# sensorboard_22sch.net
KiCad netlist of a schematic drawn in EAGLE
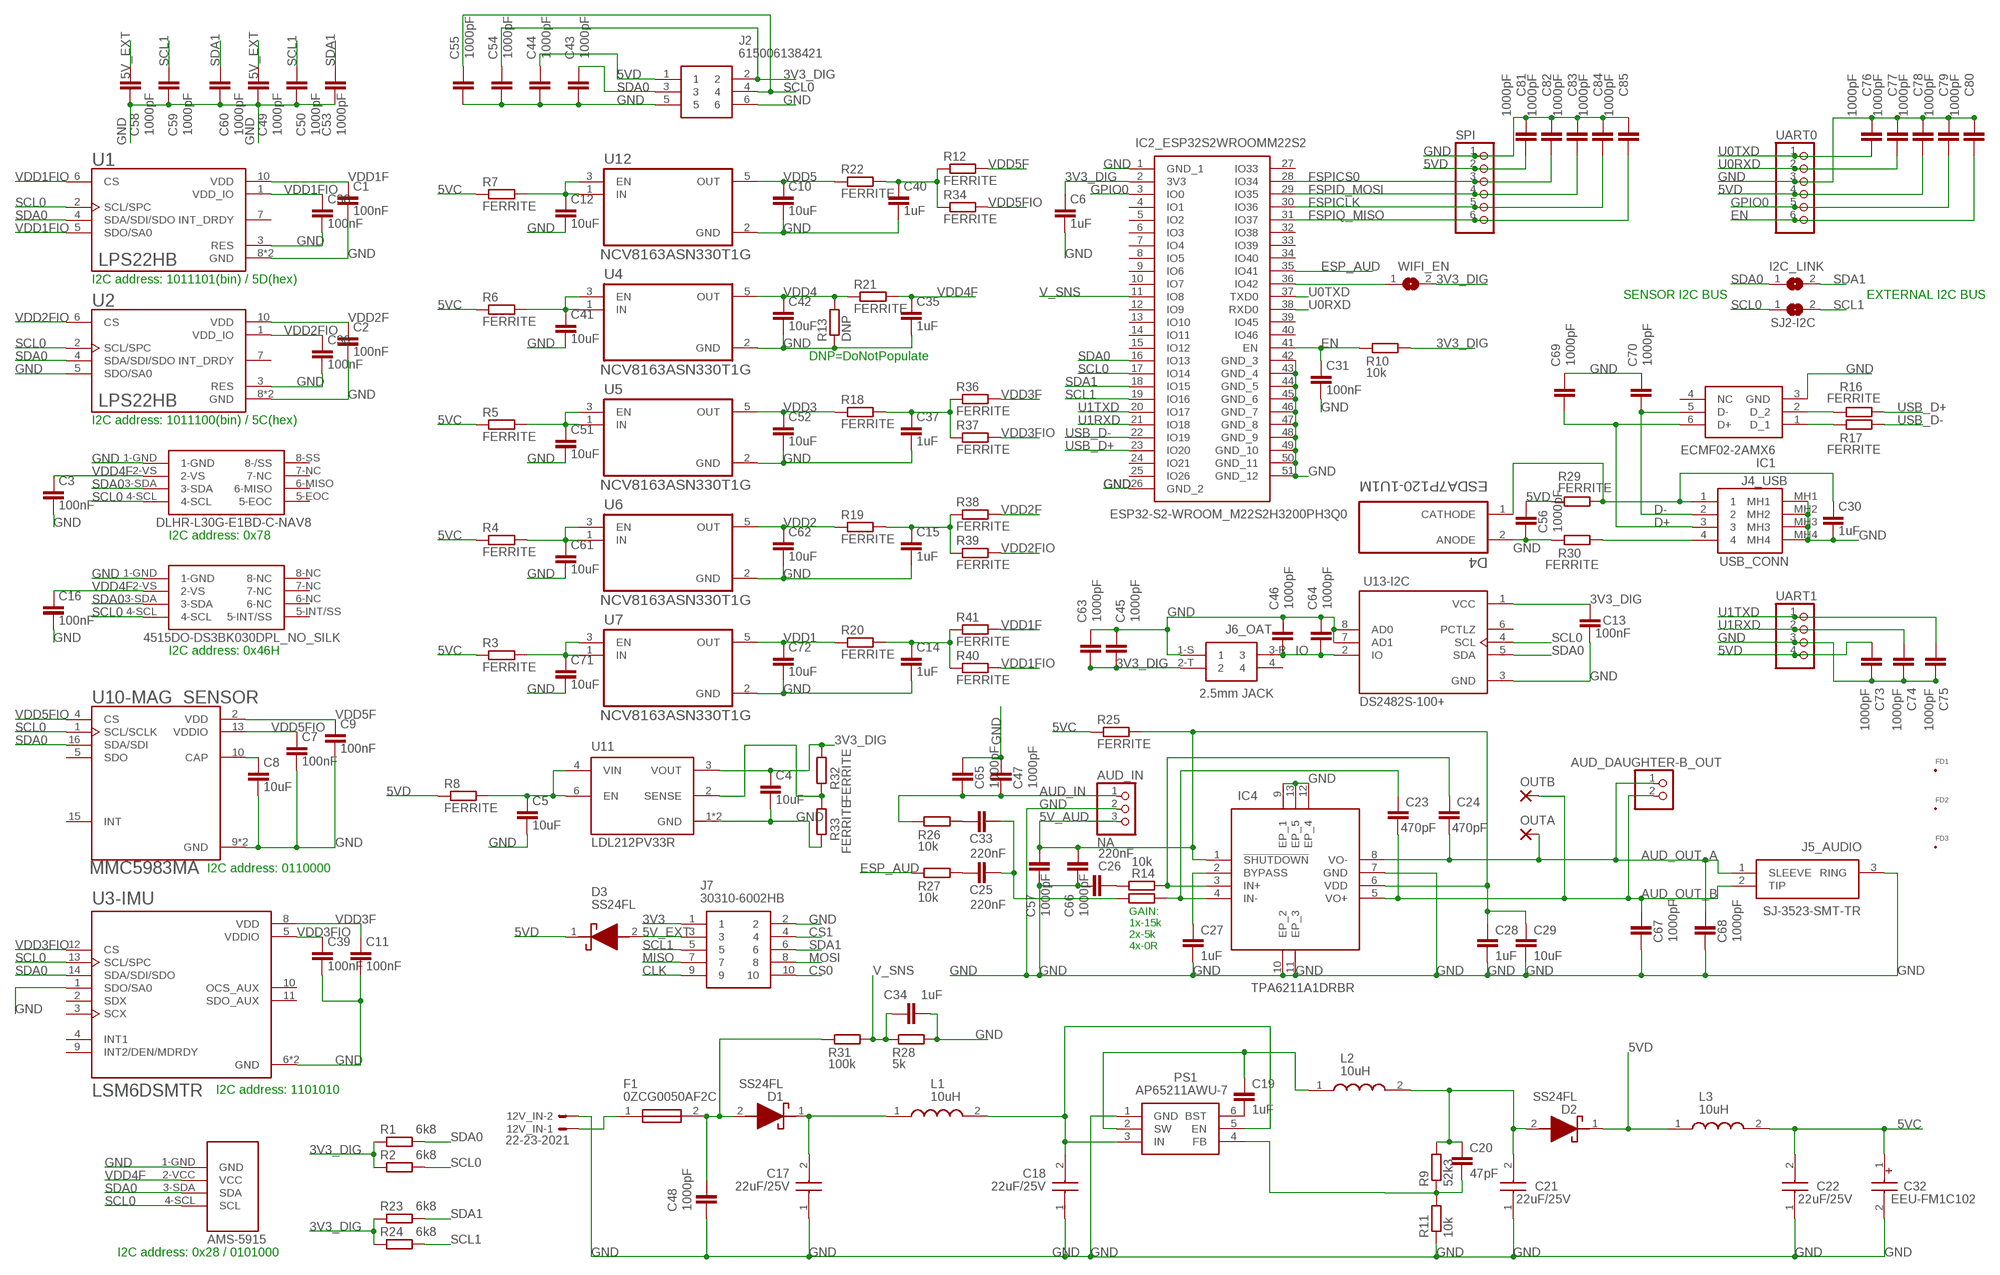
[diagram p0: schematic, sheet 1]

(export (version "E")
  (design (tool "Eeschema 10.0.6"))
  (components
    (comp (ref "12V_IN")
      (value "22-23-2021")
      (footprint "eagle-import:22-23-2021")
      (fields (field (name "MF") "MOLEX"))
      (libsource (lib "eagle-import") (part "22-23-2021"))
    )
    (comp (ref "AUD_DAUGHTER-B_OUT")
      (value "PINHD-1X2")
      (footprint "eagle-import:1X02")
      (libsource (lib "eagle-import") (part "PINHD-1X2"))
    )
    (comp (ref "AUD_IN")
      (value "NA")
      (footprint "eagle-import:1X03")
      (libsource (lib "eagle-import") (part "PINHD-1X3"))
    )
    (comp (ref "C1")
      (value "100nF")
      (footprint "eagle-import:C0402")
      (libsource (lib "eagle-import") (part "C-EUC0402"))
    )
    (comp (ref "C2")
      (value "100nF")
      (footprint "eagle-import:C0402")
      (libsource (lib "eagle-import") (part "C-EUC0402"))
    )
    (comp (ref "C3")
      (value "100nF")
      (footprint "eagle-import:C0402")
      (libsource (lib "eagle-import") (part "C-EUC0402"))
    )
    (comp (ref "C4")
      (value "10uF")
      (footprint "eagle-import:C0805")
      (libsource (lib "eagle-import") (part "C-EUC0805"))
    )
    (comp (ref "C5")
      (value "10uF")
      (footprint "eagle-import:C0805")
      (libsource (lib "eagle-import") (part "C-EUC0805"))
    )
    (comp (ref "C6")
      (value "1uF")
      (footprint "eagle-import:C0603")
      (libsource (lib "eagle-import") (part "C-EUC0603"))
    )
    (comp (ref "C7")
      (value "100nF")
      (footprint "eagle-import:C0402")
      (libsource (lib "eagle-import") (part "C-EUC0402"))
    )
    (comp (ref "C8")
      (value "10uF")
      (footprint "eagle-import:C0805")
      (libsource (lib "eagle-import") (part "C-EUC0805"))
    )
    (comp (ref "C9")
      (value "100nF")
      (footprint "eagle-import:C0402")
      (libsource (lib "eagle-import") (part "C-EUC0402"))
    )
    (comp (ref "C10")
      (value "10uF")
      (footprint "eagle-import:C0805")
      (libsource (lib "eagle-import") (part "C-EUC0805"))
    )
    (comp (ref "C11")
      (value "100nF")
      (footprint "eagle-import:C0402")
      (libsource (lib "eagle-import") (part "C-EUC0402"))
    )
    (comp (ref "C12")
      (value "10uF")
      (footprint "eagle-import:C0805")
      (libsource (lib "eagle-import") (part "C-EUC0805"))
    )
    (comp (ref "C13")
      (value "100nF")
      (footprint "eagle-import:C0402")
      (libsource (lib "eagle-import") (part "C-EUC0402"))
    )
    (comp (ref "C14")
      (value "1uF")
      (footprint "eagle-import:C0603")
      (libsource (lib "eagle-import") (part "C-EUC0603"))
    )
    (comp (ref "C15")
      (value "1uF")
      (footprint "eagle-import:C0603")
      (libsource (lib "eagle-import") (part "C-EUC0603"))
    )
    (comp (ref "C16")
      (value "100nF")
      (footprint "eagle-import:C0402")
      (libsource (lib "eagle-import") (part "C-EUC0402"))
    )
    (comp (ref "C17")
      (value "22uF/25V")
      (footprint "eagle-import:CAPC3216X180N")
      (fields (field (name "MANUFACTURER_PART_NUMBER") "CL31A226KAHNNNE"))
      (libsource (lib "eagle-import") (part "CL31A226KAHNNNE"))
    )
    (comp (ref "C18")
      (value "22uF/25V")
      (footprint "eagle-import:CAPC3216X180N")
      (fields (field (name "MANUFACTURER_PART_NUMBER") "CL31A226KAHNNNE"))
      (libsource (lib "eagle-import") (part "CL31A226KAHNNNE"))
    )
    (comp (ref "C19")
      (value "1uF")
      (footprint "eagle-import:C0603")
      (libsource (lib "eagle-import") (part "C-EUC0603"))
    )
    (comp (ref "C20")
      (value "47pF")
      (footprint "eagle-import:C0402")
      (libsource (lib "eagle-import") (part "C-EUC0402"))
    )
    (comp (ref "C21")
      (value "22uF/25V")
      (footprint "eagle-import:CAPC3216X180N")
      (fields (field (name "MANUFACTURER_PART_NUMBER") "CL31A226KAHNNNE"))
      (libsource (lib "eagle-import") (part "CL31A226KAHNNNE"))
    )
    (comp (ref "C22")
      (value "22uF/25V")
      (footprint "eagle-import:CAPC3216X180N")
      (fields (field (name "MANUFACTURER_PART_NUMBER") "CL31A226KAHNNNE"))
      (libsource (lib "eagle-import") (part "CL31A226KAHNNNE"))
    )
    (comp (ref "C23")
      (value "470pF")
      (footprint "eagle-import:C0805")
      (libsource (lib "eagle-import") (part "C-EUC0805"))
    )
    (comp (ref "C24")
      (value "470pF")
      (footprint "eagle-import:C0805")
      (libsource (lib "eagle-import") (part "C-EUC0805"))
    )
    (comp (ref "C25")
      (value "220nF")
      (footprint "eagle-import:C1206")
      (libsource (lib "eagle-import") (part "C-EUC1206"))
    )
    (comp (ref "C26")
      (value "220nF")
      (footprint "eagle-import:C1206")
      (libsource (lib "eagle-import") (part "C-EUC1206"))
    )
    (comp (ref "C27")
      (value "1uF")
      (footprint "eagle-import:C0603")
      (libsource (lib "eagle-import") (part "C-EUC0603"))
    )
    (comp (ref "C28")
      (value "1uF")
      (footprint "eagle-import:C0603")
      (libsource (lib "eagle-import") (part "C-EUC0603"))
    )
    (comp (ref "C29")
      (value "10uF")
      (footprint "eagle-import:C0805")
      (libsource (lib "eagle-import") (part "C-EUC0805"))
    )
    (comp (ref "C30")
      (value "1uF")
      (footprint "eagle-import:C0603")
      (libsource (lib "eagle-import") (part "C-EUC0603"))
    )
    (comp (ref "C31")
      (value "100nF")
      (footprint "eagle-import:C0402")
      (libsource (lib "eagle-import") (part "C-EUC0402"))
    )
    (comp (ref "C32")
      (value "EEU-FM1C102")
      (footprint "eagle-import:CAPPRD500W65D1000H2200")
      (fields (field (name "MOUSER_PART_NUMBER") "667-EEU-FM1C102"))
      (libsource (lib "eagle-import") (part "EEU-FM1C102"))
    )
    (comp (ref "C33")
      (value "220nF")
      (footprint "eagle-import:C1206")
      (libsource (lib "eagle-import") (part "C-EUC1206"))
    )
    (comp (ref "C34")
      (value "1uF")
      (footprint "eagle-import:C0603")
      (libsource (lib "eagle-import") (part "C-EUC0603"))
    )
    (comp (ref "C35")
      (value "1uF")
      (footprint "eagle-import:C0603")
      (libsource (lib "eagle-import") (part "C-EUC0603"))
    )
    (comp (ref "C36")
      (value "100nF")
      (footprint "eagle-import:C0402")
      (libsource (lib "eagle-import") (part "C-EUC0402"))
    )
    (comp (ref "C37")
      (value "1uF")
      (footprint "eagle-import:C0603")
      (libsource (lib "eagle-import") (part "C-EUC0603"))
    )
    (comp (ref "C38")
      (value "100nF")
      (footprint "eagle-import:C0402")
      (libsource (lib "eagle-import") (part "C-EUC0402"))
    )
    (comp (ref "C39")
      (value "100nF")
      (footprint "eagle-import:C0402")
      (libsource (lib "eagle-import") (part "C-EUC0402"))
    )
    (comp (ref "C40")
      (value "1uF")
      (footprint "eagle-import:C0603")
      (libsource (lib "eagle-import") (part "C-EUC0603"))
    )
    (comp (ref "C41")
      (value "10uF")
      (footprint "eagle-import:C0805")
      (libsource (lib "eagle-import") (part "C-EUC0805"))
    )
    (comp (ref "C42")
      (value "10uF")
      (footprint "eagle-import:C0805")
      (libsource (lib "eagle-import") (part "C-EUC0805"))
    )
    (comp (ref "C43")
      (value "1000pF")
      (footprint "eagle-import:C0402")
      (libsource (lib "eagle-import") (part "C-EUC0402"))
    )
    (comp (ref "C44")
      (value "1000pF")
      (footprint "eagle-import:C0402")
      (libsource (lib "eagle-import") (part "C-EUC0402"))
    )
    (comp (ref "C45")
      (value "1000pF")
      (footprint "eagle-import:C0402")
      (libsource (lib "eagle-import") (part "C-EUC0402"))
    )
    (comp (ref "C46")
      (value "1000pF")
      (footprint "eagle-import:C0402")
      (libsource (lib "eagle-import") (part "C-EUC0402"))
    )
    (comp (ref "C47")
      (value "1000pF")
      (footprint "eagle-import:C0402")
      (libsource (lib "eagle-import") (part "C-EUC0402"))
    )
    (comp (ref "C48")
      (value "1000pF")
      (footprint "eagle-import:C0402")
      (libsource (lib "eagle-import") (part "C-EUC0402"))
    )
    (comp (ref "C49")
      (value "1000pF")
      (footprint "eagle-import:C0402")
      (libsource (lib "eagle-import") (part "C-EUC0402"))
    )
    (comp (ref "C50")
      (value "1000pF")
      (footprint "eagle-import:C0402")
      (libsource (lib "eagle-import") (part "C-EUC0402"))
    )
    (comp (ref "C51")
      (value "10uF")
      (footprint "eagle-import:C0805")
      (libsource (lib "eagle-import") (part "C-EUC0805"))
    )
    (comp (ref "C52")
      (value "10uF")
      (footprint "eagle-import:C0805")
      (libsource (lib "eagle-import") (part "C-EUC0805"))
    )
    (comp (ref "C53")
      (value "1000pF")
      (footprint "eagle-import:C0402")
      (libsource (lib "eagle-import") (part "C-EUC0402"))
    )
    (comp (ref "C54")
      (value "1000pF")
      (footprint "eagle-import:C0402")
      (libsource (lib "eagle-import") (part "C-EUC0402"))
    )
    (comp (ref "C55")
      (value "1000pF")
      (footprint "eagle-import:C0402")
      (libsource (lib "eagle-import") (part "C-EUC0402"))
    )
    (comp (ref "C56")
      (value "1000pF")
      (footprint "eagle-import:C0402")
      (libsource (lib "eagle-import") (part "C-EUC0402"))
    )
    (comp (ref "C57")
      (value "1000pF")
      (footprint "eagle-import:C0402")
      (libsource (lib "eagle-import") (part "C-EUC0402"))
    )
    (comp (ref "C58")
      (value "1000pF")
      (footprint "eagle-import:C0402")
      (libsource (lib "eagle-import") (part "C-EUC0402"))
    )
    (comp (ref "C59")
      (value "1000pF")
      (footprint "eagle-import:C0402")
      (libsource (lib "eagle-import") (part "C-EUC0402"))
    )
    (comp (ref "C60")
      (value "1000pF")
      (footprint "eagle-import:C0402")
      (libsource (lib "eagle-import") (part "C-EUC0402"))
    )
    (comp (ref "C61")
      (value "10uF")
      (footprint "eagle-import:C0805")
      (libsource (lib "eagle-import") (part "C-EUC0805"))
    )
    (comp (ref "C62")
      (value "10uF")
      (footprint "eagle-import:C0805")
      (libsource (lib "eagle-import") (part "C-EUC0805"))
    )
    (comp (ref "C63")
      (value "1000pF")
      (footprint "eagle-import:C0402")
      (libsource (lib "eagle-import") (part "C-EUC0402"))
    )
    (comp (ref "C64")
      (value "1000pF")
      (footprint "eagle-import:C0402")
      (libsource (lib "eagle-import") (part "C-EUC0402"))
    )
    (comp (ref "C65")
      (value "1000pF")
      (footprint "eagle-import:C0402")
      (libsource (lib "eagle-import") (part "C-EUC0402"))
    )
    (comp (ref "C66")
      (value "1000pF")
      (footprint "eagle-import:C0402")
      (libsource (lib "eagle-import") (part "C-EUC0402"))
    )
    (comp (ref "C67")
      (value "1000pF")
      (footprint "eagle-import:C0402")
      (libsource (lib "eagle-import") (part "C-EUC0402"))
    )
    (comp (ref "C68")
      (value "1000pF")
      (footprint "eagle-import:C0402")
      (libsource (lib "eagle-import") (part "C-EUC0402"))
    )
    (comp (ref "C69")
      (value "1000pF")
      (footprint "eagle-import:C0402")
      (libsource (lib "eagle-import") (part "C-EUC0402"))
    )
    (comp (ref "C70")
      (value "1000pF")
      (footprint "eagle-import:C0402")
      (libsource (lib "eagle-import") (part "C-EUC0402"))
    )
    (comp (ref "C71")
      (value "10uF")
      (footprint "eagle-import:C0805")
      (libsource (lib "eagle-import") (part "C-EUC0805"))
    )
    (comp (ref "C72")
      (value "10uF")
      (footprint "eagle-import:C0805")
      (libsource (lib "eagle-import") (part "C-EUC0805"))
    )
    (comp (ref "C73")
      (value "1000pF")
      (footprint "eagle-import:C0402")
      (libsource (lib "eagle-import") (part "C-EUC0402"))
    )
    (comp (ref "C74")
      (value "1000pF")
      (footprint "eagle-import:C0402")
      (libsource (lib "eagle-import") (part "C-EUC0402"))
    )
    (comp (ref "C75")
      (value "1000pF")
      (footprint "eagle-import:C0402")
      (libsource (lib "eagle-import") (part "C-EUC0402"))
    )
    (comp (ref "C76")
      (value "1000pF")
      (footprint "eagle-import:C0402")
      (libsource (lib "eagle-import") (part "C-EUC0402"))
    )
    (comp (ref "C77")
      (value "1000pF")
      (footprint "eagle-import:C0402")
      (libsource (lib "eagle-import") (part "C-EUC0402"))
    )
    (comp (ref "C78")
      (value "1000pF")
      (footprint "eagle-import:C0402")
      (libsource (lib "eagle-import") (part "C-EUC0402"))
    )
    (comp (ref "C79")
      (value "1000pF")
      (footprint "eagle-import:C0402")
      (libsource (lib "eagle-import") (part "C-EUC0402"))
    )
    (comp (ref "C80")
      (value "1000pF")
      (footprint "eagle-import:C0402")
      (libsource (lib "eagle-import") (part "C-EUC0402"))
    )
    (comp (ref "C81")
      (value "1000pF")
      (footprint "eagle-import:C0402")
      (libsource (lib "eagle-import") (part "C-EUC0402"))
    )
    (comp (ref "C82")
      (value "1000pF")
      (footprint "eagle-import:C0402")
      (libsource (lib "eagle-import") (part "C-EUC0402"))
    )
    (comp (ref "C83")
      (value "1000pF")
      (footprint "eagle-import:C0402")
      (libsource (lib "eagle-import") (part "C-EUC0402"))
    )
    (comp (ref "C84")
      (value "1000pF")
      (footprint "eagle-import:C0402")
      (libsource (lib "eagle-import") (part "C-EUC0402"))
    )
    (comp (ref "C85")
      (value "1000pF")
      (footprint "eagle-import:C0402")
      (libsource (lib "eagle-import") (part "C-EUC0402"))
    )
    (comp (ref "D1")
      (value "SS24FL")
      (footprint "eagle-import:SODFL3617X108N")
      (fields (field (name "MOUSER_PART_NUMBER") "512-SS24FL"))
      (libsource (lib "eagle-import") (part "SS24FL"))
    )
    (comp (ref "D2")
      (value "SS24FL")
      (footprint "eagle-import:SODFL3617X108N")
      (fields (field (name "MOUSER_PART_NUMBER") "512-SS24FL"))
      (libsource (lib "eagle-import") (part "SS24FL"))
    )
    (comp (ref "D3")
      (value "SS24FL")
      (footprint "eagle-import:SODFL3617X108N")
      (fields (field (name "MOUSER_PART_NUMBER") "512-SS24FL"))
      (libsource (lib "eagle-import") (part "SS24FL"))
    )
    (comp (ref "D4")
      (value "ESDA7P120-1U1M")
      (footprint "eagle-import:DIO_ESDA13P70-1U1M")
      (fields (field (name "MF") "STMicroelectronics"))
      (libsource (lib "eagle-import") (part "ESDA7P120-1U1M"))
    )
    (comp (ref "DLHR-L30G-E1BD-C-NAV8")
      (value "DLHR-L30G-E1BD-C-NAV8")
      (footprint "eagle-import:DLHR-L30G-E1BD-C-NAV8")
      (libsource (lib "eagle-import") (part "DLHR-L30G-E1BD-C-NAV8"))
    )
    (comp (ref "F1")
      (value "0ZCG0050AF2C")
      (footprint "eagle-import:FUSC4632X75N")
      (fields (field (name "MOUSER_PART_NUMBER") "530-0ZCG0050AF2C"))
      (libsource (lib "eagle-import") (part "0ZCG0050AF2C"))
    )
    (comp (ref "FD1")
      (value "FID_20MIL_P")
      (footprint "eagle-import:FID_020_P")
      (libsource (lib "eagle-import") (part "FID_20MIL_P"))
    )
    (comp (ref "FD2")
      (value "FID_20MIL_P")
      (footprint "eagle-import:FID_020_P")
      (libsource (lib "eagle-import") (part "FID_20MIL_P"))
    )
    (comp (ref "FD3")
      (value "FID_20MIL_P")
      (footprint "eagle-import:FID_020_P")
      (libsource (lib "eagle-import") (part "FID_20MIL_P"))
    )
    (comp (ref "I2C_LINK")
      (value "SJ")
      (footprint "eagle-import:SJ")
      (libsource (lib "eagle-import") (part "SJ"))
    )
    (comp (ref "IC1")
      (value "ECMF02-2AMX6")
      (footprint "eagle-import:SON50P150X170X55-6N")
      (fields (field (name "MF") "STMicroelectronics"))
      (libsource (lib "eagle-import") (part "ECMF02-2AMX6"))
    )
    (comp (ref "IC2_ESP32S2WROOMM22S2")
      (value "ESP32-S2-WROOM_M22S2H3200PH3Q0")
      (footprint "eagle-import:ESP32S2WROOMM22S2H3200PH3Q0")
      (fields
        (field (name "MANUFACTURER_PART_NUMBER") "ESP32-S2-WROOM(M22S2H3200PH3Q0)")
        (field (name "MOUSER_PART_NUMBER") "356-ESP32S2WRM3200PH")
      )
      (libsource (lib "eagle-import") (part "ESP32-S2-WROOM_M22S2H3200PH3Q0"))
    )
    (comp (ref "IC4")
      (value "TPA6211A1DRBR")
      (footprint "eagle-import:TPS7A8033DRBT")
      (fields (field (name "MOUSER_PART_NUMBER") "595-TPA6211A1DRBR"))
      (libsource (lib "eagle-import") (part "TPA6211A1DRBR"))
    )
    (comp (ref "J2")
      (value "615006138421")
      (footprint "eagle-import:615006138421")
      (fields (field (name "MOUSER_PART_NUMBER") "710-615006138421"))
      (libsource (lib "eagle-import") (part "615006138421"))
    )
    (comp (ref "J4_USB")
      (value "USB_CONN")
      (footprint "eagle-import:737250110BLF")
      (fields
        (field (name "MANUFACTURER_PART_NUMBER") "73725-0110BLF")
        (field (name "MOUSER_PART_NUMBER") "649-73725-0110BLF")
      )
      (libsource (lib "eagle-import") (part "73725-0110BLF"))
    )
    (comp (ref "J5_AUDIO")
      (value "SJ-3523-SMT-TR")
      (footprint "eagle-import:SJ3523SMTTR")
      (fields (field (name "MOUSER_PART_NUMBER") "490-SJ-3523-SMT-TR"))
      (libsource (lib "eagle-import") (part "SJ-3523-SMT-TR"))
    )
    (comp (ref "J6_OAT")
      (value "2.5mm JACK")
      (footprint "eagle-import:SJ-2523-SMT-TR")
      (fields
        (field (name "MANUFACTURER_PART_NUMBER") "SJ-2523-SMT-TR")
        (field (name "MOUSER_PART_NUMBER") "490-SJ-2523-SMT-TR")
      )
      (libsource (lib "eagle-import") (part "SJ-2523-SMT-TR"))
    )
    (comp (ref "J7")
      (value "30310-6002HB")
      (footprint "eagle-import:SHDR10W64P254_2X5_2030X878X930")
      (fields (field (name "MOUSER_PART_NUMBER") "517-30310-6002"))
      (libsource (lib "eagle-import") (part "30310-6002HB"))
    )
    (comp (ref "L1")
      (value "10uH")
      (footprint "eagle-import:FDSD0420WH150MP3")
      (fields
        (field (name "MANUFACTURER_PART_NUMBER") "FDSD0420-H-100M=P3")
        (field (name "MOUSER_PART_NUMBER") "81-FDSD0420-H-100MP3")
      )
      (libsource (lib "eagle-import") (part "FDSD0420-H-100M=P3"))
    )
    (comp (ref "L2")
      (value "10uH")
      (footprint "eagle-import:FDSD0420WH150MP3")
      (fields
        (field (name "MANUFACTURER_PART_NUMBER") "FDSD0420-H-100M=P3")
        (field (name "MOUSER_PART_NUMBER") "81-FDSD0420-H-100MP3")
      )
      (libsource (lib "eagle-import") (part "FDSD0420-H-100M=P3"))
    )
    (comp (ref "L3")
      (value "10uH")
      (footprint "eagle-import:FDSD0420WH150MP3")
      (fields
        (field (name "MANUFACTURER_PART_NUMBER") "FDSD0420-H-100M=P3")
        (field (name "MOUSER_PART_NUMBER") "81-FDSD0420-H-100MP3")
      )
      (libsource (lib "eagle-import") (part "FDSD0420-H-100M=P3"))
    )
    (comp (ref "OUTA")
      (value "SMD2_SMALLSMALL")
      (footprint "eagle-import:SMD2_SMALL")
      (libsource (lib "eagle-import") (part "SMD2_SMALLSMALL"))
    )
    (comp (ref "OUTB")
      (value "SMD2_SMALLSMALL")
      (footprint "eagle-import:SMD2_SMALL")
      (libsource (lib "eagle-import") (part "SMD2_SMALLSMALL"))
    )
    (comp (ref "PS1")
      (value "AP65211AWU-7")
      (footprint "eagle-import:SOT95P280X90-6N")
      (fields (field (name "MOUSER_PART_NUMBER") "621-AP65211AWU-7"))
      (libsource (lib "eagle-import") (part "AP65211AWU-7"))
    )
    (comp (ref "R1")
      (value "6k8")
      (footprint "eagle-import:R0402")
      (libsource (lib "eagle-import") (part "R-EU_R0402"))
    )
    (comp (ref "R2")
      (value "6k8")
      (footprint "eagle-import:R0402")
      (libsource (lib "eagle-import") (part "R-EU_R0402"))
    )
    (comp (ref "R3")
      (value "FERRITE")
      (footprint "eagle-import:R0805")
      (libsource (lib "eagle-import") (part "R-EU_R0805"))
    )
    (comp (ref "R4")
      (value "FERRITE")
      (footprint "eagle-import:R0805")
      (libsource (lib "eagle-import") (part "R-EU_R0805"))
    )
    (comp (ref "R5")
      (value "FERRITE")
      (footprint "eagle-import:R0805")
      (libsource (lib "eagle-import") (part "R-EU_R0805"))
    )
    (comp (ref "R6")
      (value "FERRITE")
      (footprint "eagle-import:R0805")
      (libsource (lib "eagle-import") (part "R-EU_R0805"))
    )
    (comp (ref "R7")
      (value "FERRITE")
      (footprint "eagle-import:R0805")
      (libsource (lib "eagle-import") (part "R-EU_R0805"))
    )
    (comp (ref "R8")
      (value "FERRITE")
      (footprint "eagle-import:R0805")
      (libsource (lib "eagle-import") (part "R-EU_R0805"))
    )
    (comp (ref "R9")
      (value "52k3")
      (footprint "eagle-import:R0402")
      (libsource (lib "eagle-import") (part "R-EU_R0402"))
    )
    (comp (ref "R10")
      (value "10k")
      (footprint "eagle-import:R0402")
      (libsource (lib "eagle-import") (part "R-EU_R0402"))
    )
    (comp (ref "R11")
      (value "10k")
      (footprint "eagle-import:R0402")
      (libsource (lib "eagle-import") (part "R-EU_R0402"))
    )
    (comp (ref "R12")
      (value "FERRITE")
      (footprint "eagle-import:R0805")
      (libsource (lib "eagle-import") (part "R-EU_R0805"))
    )
    (comp (ref "R13")
      (value "DNP")
      (footprint "eagle-import:R0805")
      (libsource (lib "eagle-import") (part "R-EU_R0805"))
    )
    (comp (ref "R14")
      (value "10k")
      (footprint "eagle-import:R0402")
      (libsource (lib "eagle-import") (part "R-EU_R0402"))
    )
    (comp (ref "R15")
      (value "R-EU_R0402")
      (footprint "eagle-import:R0402")
      (libsource (lib "eagle-import") (part "R-EU_R0402"))
    )
    (comp (ref "R16")
      (value "FERRITE")
      (footprint "eagle-import:R0805")
      (libsource (lib "eagle-import") (part "R-EU_R0805"))
    )
    (comp (ref "R17")
      (value "FERRITE")
      (footprint "eagle-import:R0805")
      (libsource (lib "eagle-import") (part "R-EU_R0805"))
    )
    (comp (ref "R18")
      (value "FERRITE")
      (footprint "eagle-import:R0805")
      (libsource (lib "eagle-import") (part "R-EU_R0805"))
    )
    (comp (ref "R19")
      (value "FERRITE")
      (footprint "eagle-import:R0805")
      (libsource (lib "eagle-import") (part "R-EU_R0805"))
    )
    (comp (ref "R20")
      (value "FERRITE")
      (footprint "eagle-import:R0805")
      (libsource (lib "eagle-import") (part "R-EU_R0805"))
    )
    (comp (ref "R21")
      (value "FERRITE")
      (footprint "eagle-import:R0805")
      (libsource (lib "eagle-import") (part "R-EU_R0805"))
    )
    (comp (ref "R22")
      (value "FERRITE")
      (footprint "eagle-import:R0805")
      (libsource (lib "eagle-import") (part "R-EU_R0805"))
    )
    (comp (ref "R23")
      (value "6k8")
      (footprint "eagle-import:R0402")
      (libsource (lib "eagle-import") (part "R-EU_R0402"))
    )
    (comp (ref "R24")
      (value "6k8")
      (footprint "eagle-import:R0402")
      (libsource (lib "eagle-import") (part "R-EU_R0402"))
    )
    (comp (ref "R25")
      (value "FERRITE")
      (footprint "eagle-import:R0805")
      (libsource (lib "eagle-import") (part "R-EU_R0805"))
    )
    (comp (ref "R26")
      (value "10k")
      (footprint "eagle-import:R0402")
      (libsource (lib "eagle-import") (part "R-EU_R0402"))
    )
    (comp (ref "R27")
      (value "10k")
      (footprint "eagle-import:R0402")
      (libsource (lib "eagle-import") (part "R-EU_R0402"))
    )
    (comp (ref "R28")
      (value "5k")
      (footprint "eagle-import:R0402")
      (libsource (lib "eagle-import") (part "R-EU_R0402"))
    )
    (comp (ref "R29")
      (value "FERRITE")
      (footprint "eagle-import:R0805")
      (libsource (lib "eagle-import") (part "R-EU_R0805"))
    )
    (comp (ref "R30")
      (value "FERRITE")
      (footprint "eagle-import:R0805")
      (libsource (lib "eagle-import") (part "R-EU_R0805"))
    )
    (comp (ref "R31")
      (value "100k")
      (footprint "eagle-import:R0402")
      (libsource (lib "eagle-import") (part "R-EU_R0402"))
    )
    (comp (ref "R32")
      (value "FERRITE")
      (footprint "eagle-import:R0402")
      (libsource (lib "eagle-import") (part "R-EU_R0402"))
    )
    (comp (ref "R33")
      (value "FERRITE")
      (footprint "eagle-import:R0402")
      (libsource (lib "eagle-import") (part "R-EU_R0402"))
    )
    (comp (ref "R34")
      (value "FERRITE")
      (footprint "eagle-import:R0805")
      (libsource (lib "eagle-import") (part "R-EU_R0805"))
    )
    (comp (ref "R36")
      (value "FERRITE")
      (footprint "eagle-import:R0805")
      (libsource (lib "eagle-import") (part "R-EU_R0805"))
    )
    (comp (ref "R37")
      (value "FERRITE")
      (footprint "eagle-import:R0805")
      (libsource (lib "eagle-import") (part "R-EU_R0805"))
    )
    (comp (ref "R38")
      (value "FERRITE")
      (footprint "eagle-import:R0805")
      (libsource (lib "eagle-import") (part "R-EU_R0805"))
    )
    (comp (ref "R39")
      (value "FERRITE")
      (footprint "eagle-import:R0805")
      (libsource (lib "eagle-import") (part "R-EU_R0805"))
    )
    (comp (ref "R40")
      (value "FERRITE")
      (footprint "eagle-import:R0805")
      (libsource (lib "eagle-import") (part "R-EU_R0805"))
    )
    (comp (ref "R41")
      (value "FERRITE")
      (footprint "eagle-import:R0805")
      (libsource (lib "eagle-import") (part "R-EU_R0805"))
    )
    (comp (ref "SJ2-I2C")
      (value "SJ")
      (footprint "eagle-import:SJ")
      (libsource (lib "eagle-import") (part "SJ"))
    )
    (comp (ref "SPI")
      (value "PINHD-1X6")
      (footprint "eagle-import:1X06")
      (libsource (lib "eagle-import") (part "PINHD-1X6"))
    )
    (comp (ref "U$1")
      (value "AMS-5915")
      (footprint "eagle-import:AMS-5915")
      (libsource (lib "eagle-import") (part "AMS-5915"))
    )
    (comp (ref "U$4")
      (value "4515DO-DS3BK030DPL_NO_SILKNO_SILK")
      (footprint "eagle-import:4515DO-DS3BK030DPL_NO_SILK")
      (libsource (lib "eagle-import") (part "4515DO-DS3BK030DPL_NO_SILKNO_SILK"))
    )
    (comp (ref "U1")
      (value "LPS22HB")
      (footprint "eagle-import:LGA10R50P2X3_200X200X80")
      (fields (field (name "MF") "STMicroelectronics"))
      (libsource (lib "eagle-import") (part "LPS22HB"))
    )
    (comp (ref "U2")
      (value "LPS22HB")
      (footprint "eagle-import:LGA10R50P2X3_200X200X80")
      (fields (field (name "MF") "STMicroelectronics"))
      (libsource (lib "eagle-import") (part "LPS22HB"))
    )
    (comp (ref "U3-IMU")
      (value "LSM6DSMTR")
      (footprint "eagle-import:PQFN50P300X250X86-14N")
      (fields (field (name "MF") "STMicroelectronics"))
      (libsource (lib "eagle-import") (part "LSM6DSMTR"))
    )
    (comp (ref "U4")
      (value "NCV8163ASN330T1G")
      (footprint "eagle-import:SOP95P275X110-5N")
      (fields (field (name "MF") "ON Semiconductor"))
      (libsource (lib "eagle-import") (part "NCV8163ASN330T1G"))
    )
    (comp (ref "U5")
      (value "NCV8163ASN330T1G")
      (footprint "eagle-import:SOP95P275X110-5N")
      (fields (field (name "MF") "ON Semiconductor"))
      (libsource (lib "eagle-import") (part "NCV8163ASN330T1G"))
    )
    (comp (ref "U6")
      (value "NCV8163ASN330T1G")
      (footprint "eagle-import:SOP95P275X110-5N")
      (fields (field (name "MF") "ON Semiconductor"))
      (libsource (lib "eagle-import") (part "NCV8163ASN330T1G"))
    )
    (comp (ref "U7")
      (value "NCV8163ASN330T1G")
      (footprint "eagle-import:SOP95P275X110-5N")
      (fields (field (name "MF") "ON Semiconductor"))
      (libsource (lib "eagle-import") (part "NCV8163ASN330T1G"))
    )
    (comp (ref "U10-MAG_SENSOR")
      (value "MMC5983MA")
      (footprint "eagle-import:LGA16R50P4X4_330X330X100")
      (fields (field (name "MF") "ON Semiconductor") (field (name "MP") "FIS1100"))
      (libsource (lib "eagle-import") (part "MMC5983MA"))
    )
    (comp (ref "U11")
      (value "LDL212PV33R")
      (footprint "eagle-import:SON50P200X200X80-7N")
      (fields (field (name "MF") "STMicroelectronics"))
      (libsource (lib "eagle-import") (part "LDL212PV33R"))
    )
    (comp (ref "U12")
      (value "NCV8163ASN330T1G")
      (footprint "eagle-import:SOP95P275X110-5N")
      (fields (field (name "MF") "ON Semiconductor"))
      (libsource (lib "eagle-import") (part "NCV8163ASN330T1G"))
    )
    (comp (ref "U13-I2C")
      (value "DS2482S-100+")
      (footprint "eagle-import:SOIC127P600X175-8N")
      (fields (field (name "MF") "Maxim Integrated"))
      (libsource (lib "eagle-import") (part "DS2482S-100+"))
    )
    (comp (ref "UART0")
      (value "PINHD-1X6")
      (footprint "eagle-import:1X06")
      (libsource (lib "eagle-import") (part "PINHD-1X6"))
    )
    (comp (ref "UART1")
      (value "PINHD-1X4")
      (footprint "eagle-import:1X04")
      (libsource (lib "eagle-import") (part "PINHD-1X4"))
    )
    (comp (ref "WIFI_EN")
      (value "SJ")
      (footprint "eagle-import:SJ")
      (libsource (lib "eagle-import") (part "SJ"))
    )
  )
  (nets
    (net (code "1") (name "/3V3") (class "Default")
      (node (ref "J7") (pin "1") (pinfunction "1_1") (pintype "bidirectional"))
    )
    (net (code "2") (name "/3V3_DIG") (class "Default")
      (node (ref "C13") (pin "1") (pinfunction "1_1") (pintype "passive"))
      (node (ref "C4") (pin "1") (pinfunction "1_1") (pintype "passive"))
      (node (ref "C45") (pin "1") (pinfunction "1_1") (pintype "passive"))
      (node (ref "C54") (pin "2") (pinfunction "2_2") (pintype "passive"))
      (node (ref "C6") (pin "1") (pinfunction "1_1") (pintype "passive"))
      (node (ref "C63") (pin "1") (pinfunction "1_1") (pintype "passive"))
      (node (ref "IC2_ESP32S2WROOMM22S2") (pin "2") (pinfunction "3V3_2") (pintype "bidirectional"))
      (node (ref "J2") (pin "2") (pinfunction "2_2") (pintype "bidirectional"))
      (node (ref "J6_OAT") (pin "2-T") (pinfunction "2_2-T") (pintype "bidirectional"))
      (node (ref "R1") (pin "1") (pinfunction "1_1") (pintype "passive"))
      (node (ref "R10") (pin "2") (pinfunction "2_2") (pintype "passive"))
      (node (ref "R2") (pin "1") (pinfunction "1_1") (pintype "passive"))
      (node (ref "R23") (pin "1") (pinfunction "1_1") (pintype "passive"))
      (node (ref "R24") (pin "1") (pinfunction "1_1") (pintype "passive"))
      (node (ref "R32") (pin "2") (pinfunction "2_2") (pintype "passive"))
      (node (ref "U11") (pin "3") (pinfunction "VOUT_3") (pintype "output"))
      (node (ref "U13-I2C") (pin "1") (pinfunction "VCC_1") (pintype "power_in"))
      (node (ref "WIFI_EN") (pin "2") (pinfunction "2_2") (pintype "passive"))
    )
    (net (code "3") (name "/5VC") (class "Default")
      (node (ref "C22") (pin "2") (pinfunction "2_2") (pintype "bidirectional"))
      (node (ref "C32") (pin "1") (pinfunction "+_1") (pintype "bidirectional"))
      (node (ref "L3") (pin "2") (pinfunction "2_2") (pintype "bidirectional"))
      (node (ref "R25") (pin "1") (pinfunction "1_1") (pintype "passive"))
      (node (ref "R3") (pin "1") (pinfunction "1_1") (pintype "passive"))
      (node (ref "R4") (pin "1") (pinfunction "1_1") (pintype "passive"))
      (node (ref "R5") (pin "1") (pinfunction "1_1") (pintype "passive"))
      (node (ref "R6") (pin "1") (pinfunction "1_1") (pintype "passive"))
      (node (ref "R7") (pin "1") (pinfunction "1_1") (pintype "passive"))
    )
    (net (code "4") (name "/5VD") (class "Default")
      (node (ref "C44") (pin "2") (pinfunction "2_2") (pintype "passive"))
      (node (ref "C56") (pin "2") (pinfunction "2_2") (pintype "passive"))
      (node (ref "C73") (pin "1") (pinfunction "1_1") (pintype "passive"))
      (node (ref "C78") (pin "2") (pinfunction "2_2") (pintype "passive"))
      (node (ref "C81") (pin "2") (pinfunction "2_2") (pintype "passive"))
      (node (ref "D2") (pin "1") (pinfunction "K_1") (pintype "bidirectional"))
      (node (ref "D3") (pin "1") (pinfunction "K_1") (pintype "bidirectional"))
      (node (ref "J2") (pin "1") (pinfunction "1_1") (pintype "bidirectional"))
      (node (ref "L3") (pin "1") (pinfunction "1_1") (pintype "bidirectional"))
      (node (ref "R29") (pin "1") (pinfunction "1_1") (pintype "passive"))
      (node (ref "R8") (pin "1") (pinfunction "1_1") (pintype "passive"))
      (node (ref "SPI") (pin "2") (pinfunction "2_2") (pintype "passive"))
      (node (ref "UART0") (pin "4") (pinfunction "4_4") (pintype "passive"))
      (node (ref "UART1") (pin "4") (pinfunction "4_4") (pintype "passive"))
    )
    (net (code "5") (name "/5V_AUD") (class "Default")
      (node (ref "AUD_IN") (pin "3") (pinfunction "3_3") (pintype "passive"))
      (node (ref "C28") (pin "1") (pinfunction "1_1") (pintype "passive"))
      (node (ref "C29") (pin "1") (pinfunction "1_1") (pintype "passive"))
      (node (ref "C57") (pin "2") (pinfunction "2_2") (pintype "passive"))
      (node (ref "C66") (pin "2") (pinfunction "2_2") (pintype "passive"))
      (node (ref "IC4") (pin "1") (pinfunction "~{SHUTDOWN}_1") (pintype "bidirectional"))
      (node (ref "IC4") (pin "6") (pinfunction "VDD_6") (pintype "bidirectional"))
      (node (ref "R25") (pin "2") (pinfunction "2_2") (pintype "passive"))
    )
    (net (code "6") (name "/5V_EXT") (class "Default")
      (node (ref "C49") (pin "2") (pinfunction "2_2") (pintype "passive"))
      (node (ref "C58") (pin "2") (pinfunction "2_2") (pintype "passive"))
      (node (ref "D3") (pin "2") (pinfunction "A_2") (pintype "bidirectional"))
      (node (ref "J7") (pin "3") (pinfunction "3_3") (pintype "bidirectional"))
    )
    (net (code "7") (name "/AUD_IN") (class "Default")
      (node (ref "AUD_IN") (pin "1") (pinfunction "1_1") (pintype "passive"))
      (node (ref "C47") (pin "1") (pinfunction "1_1") (pintype "passive"))
      (node (ref "C65") (pin "1") (pinfunction "1_1") (pintype "passive"))
      (node (ref "R26") (pin "1") (pinfunction "1_1") (pintype "passive"))
    )
    (net (code "8") (name "/AUD_OUT_A") (class "Default")
      (node (ref "AUD_DAUGHTER-B_OUT") (pin "1") (pinfunction "1_1") (pintype "passive"))
      (node (ref "C24") (pin "2") (pinfunction "2_2") (pintype "passive"))
      (node (ref "C68") (pin "2") (pinfunction "2_2") (pintype "passive"))
      (node (ref "IC4") (pin "8") (pinfunction "VO-_8") (pintype "bidirectional"))
      (node (ref "J5_AUDIO") (pin "1") (pinfunction "SLEEVE_1") (pintype "bidirectional"))
      (node (ref "OUTA") (pin "1") (pinfunction "P_1") (pintype "passive"))
    )
    (net (code "9") (name "/AUD_OUT_B") (class "Default")
      (node (ref "AUD_DAUGHTER-B_OUT") (pin "2") (pinfunction "2_2") (pintype "passive"))
      (node (ref "C23") (pin "2") (pinfunction "2_2") (pintype "passive"))
      (node (ref "C67") (pin "2") (pinfunction "2_2") (pintype "passive"))
      (node (ref "IC4") (pin "5") (pinfunction "VO+_5") (pintype "bidirectional"))
      (node (ref "J5_AUDIO") (pin "2") (pinfunction "TIP_2") (pintype "bidirectional"))
      (node (ref "OUTB") (pin "1") (pinfunction "P_1") (pintype "passive"))
    )
    (net (code "10") (name "/CLK") (class "Default")
      (node (ref "J7") (pin "9") (pinfunction "9_9") (pintype "bidirectional"))
    )
    (net (code "11") (name "/CS0") (class "Default")
      (node (ref "J7") (pin "10") (pinfunction "10_10") (pintype "bidirectional"))
    )
    (net (code "12") (name "/CS1") (class "Default")
      (node (ref "J7") (pin "4") (pinfunction "4_4") (pintype "bidirectional"))
    )
    (net (code "13") (name "/D+") (class "Default")
      (node (ref "C69") (pin "1") (pinfunction "1_1") (pintype "passive"))
      (node (ref "IC1") (pin "6") (pinfunction "D+_6") (pintype "bidirectional"))
      (node (ref "J4_USB") (pin "3") (pinfunction "3_3") (pintype "bidirectional"))
    )
    (net (code "14") (name "/D-") (class "Default")
      (node (ref "C70") (pin "1") (pinfunction "1_1") (pintype "passive"))
      (node (ref "IC1") (pin "5") (pinfunction "D-_5") (pintype "bidirectional"))
      (node (ref "J4_USB") (pin "2") (pinfunction "2_2") (pintype "bidirectional"))
    )
    (net (code "15") (name "/EN") (class "Default")
      (node (ref "C31") (pin "1") (pinfunction "1_1") (pintype "passive"))
      (node (ref "C80") (pin "2") (pinfunction "2_2") (pintype "passive"))
      (node (ref "IC2_ESP32S2WROOMM22S2") (pin "41") (pinfunction "EN_41") (pintype "bidirectional"))
      (node (ref "R10") (pin "1") (pinfunction "1_1") (pintype "passive"))
      (node (ref "UART0") (pin "6") (pinfunction "6_6") (pintype "passive"))
    )
    (net (code "16") (name "/ESP_AUD") (class "Default")
      (node (ref "IC2_ESP32S2WROOMM22S2") (pin "35") (pinfunction "IO41_35") (pintype "bidirectional"))
      (node (ref "R27") (pin "1") (pinfunction "1_1") (pintype "passive"))
    )
    (net (code "17") (name "/FSPICLK") (class "Default")
      (node (ref "C84") (pin "2") (pinfunction "2_2") (pintype "passive"))
      (node (ref "IC2_ESP32S2WROOMM22S2") (pin "30") (pinfunction "IO36_30") (pintype "bidirectional"))
      (node (ref "SPI") (pin "5") (pinfunction "5_5") (pintype "passive"))
    )
    (net (code "18") (name "/FSPICS0") (class "Default")
      (node (ref "C82") (pin "2") (pinfunction "2_2") (pintype "passive"))
      (node (ref "IC2_ESP32S2WROOMM22S2") (pin "28") (pinfunction "IO34_28") (pintype "bidirectional"))
      (node (ref "SPI") (pin "3") (pinfunction "3_3") (pintype "passive"))
    )
    (net (code "19") (name "/FSPID_MOSI") (class "Default")
      (node (ref "C83") (pin "2") (pinfunction "2_2") (pintype "passive"))
      (node (ref "IC2_ESP32S2WROOMM22S2") (pin "29") (pinfunction "IO35_29") (pintype "bidirectional"))
      (node (ref "SPI") (pin "4") (pinfunction "4_4") (pintype "passive"))
    )
    (net (code "20") (name "/FSPIQ_MISO") (class "Default")
      (node (ref "C85") (pin "2") (pinfunction "2_2") (pintype "passive"))
      (node (ref "IC2_ESP32S2WROOMM22S2") (pin "31") (pinfunction "IO37_31") (pintype "bidirectional"))
      (node (ref "SPI") (pin "6") (pinfunction "6_6") (pintype "passive"))
    )
    (net (code "21") (name "/GND") (class "Default")
      (node (ref "12V_IN") (pin "2") (pinfunction "S_2") (pintype "passive"))
      (node (ref "AUD_IN") (pin "2") (pinfunction "2_2") (pintype "passive"))
      (node (ref "C1") (pin "2") (pinfunction "2_2") (pintype "passive"))
      (node (ref "C10") (pin "2") (pinfunction "2_2") (pintype "passive"))
      (node (ref "C11") (pin "2") (pinfunction "2_2") (pintype "passive"))
      (node (ref "C12") (pin "2") (pinfunction "2_2") (pintype "passive"))
      (node (ref "C13") (pin "2") (pinfunction "2_2") (pintype "passive"))
      (node (ref "C14") (pin "2") (pinfunction "2_2") (pintype "passive"))
      (node (ref "C15") (pin "2") (pinfunction "2_2") (pintype "passive"))
      (node (ref "C16") (pin "2") (pinfunction "2_2") (pintype "passive"))
      (node (ref "C17") (pin "1") (pinfunction "1_1") (pintype "bidirectional"))
      (node (ref "C18") (pin "1") (pinfunction "1_1") (pintype "bidirectional"))
      (node (ref "C2") (pin "2") (pinfunction "2_2") (pintype "passive"))
      (node (ref "C21") (pin "1") (pinfunction "1_1") (pintype "bidirectional"))
      (node (ref "C22") (pin "1") (pinfunction "1_1") (pintype "bidirectional"))
      (node (ref "C26") (pin "1") (pinfunction "1_1") (pintype "passive"))
      (node (ref "C27") (pin "2") (pinfunction "2_2") (pintype "passive"))
      (node (ref "C28") (pin "2") (pinfunction "2_2") (pintype "passive"))
      (node (ref "C29") (pin "2") (pinfunction "2_2") (pintype "passive"))
      (node (ref "C3") (pin "2") (pinfunction "2_2") (pintype "passive"))
      (node (ref "C30") (pin "2") (pinfunction "2_2") (pintype "passive"))
      (node (ref "C31") (pin "2") (pinfunction "2_2") (pintype "passive"))
      (node (ref "C32") (pin "2") (pinfunction "-_2") (pintype "bidirectional"))
      (node (ref "C34") (pin "2") (pinfunction "2_2") (pintype "passive"))
      (node (ref "C35") (pin "2") (pinfunction "2_2") (pintype "passive"))
      (node (ref "C36") (pin "2") (pinfunction "2_2") (pintype "passive"))
      (node (ref "C37") (pin "2") (pinfunction "2_2") (pintype "passive"))
      (node (ref "C38") (pin "2") (pinfunction "2_2") (pintype "passive"))
      (node (ref "C39") (pin "2") (pinfunction "2_2") (pintype "passive"))
      (node (ref "C4") (pin "2") (pinfunction "2_2") (pintype "passive"))
      (node (ref "C40") (pin "2") (pinfunction "2_2") (pintype "passive"))
      (node (ref "C41") (pin "2") (pinfunction "2_2") (pintype "passive"))
      (node (ref "C42") (pin "2") (pinfunction "2_2") (pintype "passive"))
      (node (ref "C43") (pin "1") (pinfunction "1_1") (pintype "passive"))
      (node (ref "C44") (pin "1") (pinfunction "1_1") (pintype "passive"))
      (node (ref "C45") (pin "2") (pinfunction "2_2") (pintype "passive"))
      (node (ref "C46") (pin "2") (pinfunction "2_2") (pintype "passive"))
      (node (ref "C47") (pin "2") (pinfunction "2_2") (pintype "passive"))
      (node (ref "C48") (pin "1") (pinfunction "1_1") (pintype "passive"))
      (node (ref "C49") (pin "1") (pinfunction "1_1") (pintype "passive"))
      (node (ref "C5") (pin "2") (pinfunction "2_2") (pintype "passive"))
      (node (ref "C50") (pin "1") (pinfunction "1_1") (pintype "passive"))
      (node (ref "C51") (pin "2") (pinfunction "2_2") (pintype "passive"))
      (node (ref "C52") (pin "2") (pinfunction "2_2") (pintype "passive"))
      (node (ref "C53") (pin "1") (pinfunction "1_1") (pintype "passive"))
      (node (ref "C54") (pin "1") (pinfunction "1_1") (pintype "passive"))
      (node (ref "C55") (pin "1") (pinfunction "1_1") (pintype "passive"))
      (node (ref "C56") (pin "1") (pinfunction "1_1") (pintype "passive"))
      (node (ref "C57") (pin "1") (pinfunction "1_1") (pintype "passive"))
      (node (ref "C58") (pin "1") (pinfunction "1_1") (pintype "passive"))
      (node (ref "C59") (pin "1") (pinfunction "1_1") (pintype "passive"))
      (node (ref "C6") (pin "2") (pinfunction "2_2") (pintype "passive"))
      (node (ref "C60") (pin "1") (pinfunction "1_1") (pintype "passive"))
      (node (ref "C61") (pin "2") (pinfunction "2_2") (pintype "passive"))
      (node (ref "C62") (pin "2") (pinfunction "2_2") (pintype "passive"))
      (node (ref "C63") (pin "2") (pinfunction "2_2") (pintype "passive"))
      (node (ref "C64") (pin "2") (pinfunction "2_2") (pintype "passive"))
      (node (ref "C65") (pin "2") (pinfunction "2_2") (pintype "passive"))
      (node (ref "C66") (pin "1") (pinfunction "1_1") (pintype "passive"))
      (node (ref "C67") (pin "1") (pinfunction "1_1") (pintype "passive"))
      (node (ref "C68") (pin "1") (pinfunction "1_1") (pintype "passive"))
      (node (ref "C69") (pin "2") (pinfunction "2_2") (pintype "passive"))
      (node (ref "C7") (pin "2") (pinfunction "2_2") (pintype "passive"))
      (node (ref "C70") (pin "2") (pinfunction "2_2") (pintype "passive"))
      (node (ref "C71") (pin "2") (pinfunction "2_2") (pintype "passive"))
      (node (ref "C72") (pin "2") (pinfunction "2_2") (pintype "passive"))
      (node (ref "C73") (pin "2") (pinfunction "2_2") (pintype "passive"))
      (node (ref "C74") (pin "2") (pinfunction "2_2") (pintype "passive"))
      (node (ref "C75") (pin "2") (pinfunction "2_2") (pintype "passive"))
      (node (ref "C76") (pin "1") (pinfunction "1_1") (pintype "passive"))
      (node (ref "C77") (pin "1") (pinfunction "1_1") (pintype "passive"))
      (node (ref "C78") (pin "1") (pinfunction "1_1") (pintype "passive"))
      (node (ref "C79") (pin "1") (pinfunction "1_1") (pintype "passive"))
      (node (ref "C8") (pin "2") (pinfunction "2_2") (pintype "passive"))
      (node (ref "C80") (pin "1") (pinfunction "1_1") (pintype "passive"))
      (node (ref "C81") (pin "1") (pinfunction "1_1") (pintype "passive"))
      (node (ref "C82") (pin "1") (pinfunction "1_1") (pintype "passive"))
      (node (ref "C83") (pin "1") (pinfunction "1_1") (pintype "passive"))
      (node (ref "C84") (pin "1") (pinfunction "1_1") (pintype "passive"))
      (node (ref "C85") (pin "1") (pinfunction "1_1") (pintype "passive"))
      (node (ref "C9") (pin "2") (pinfunction "2_2") (pintype "passive"))
      (node (ref "D4") (pin "2") (pinfunction "ANODE_2") (pintype "bidirectional"))
      (node (ref "DLHR-L30G-E1BD-C-NAV8") (pin "1-GND") (pinfunction "1-GND_1-GND") (pintype "power_in"))
      (node (ref "IC1") (pin "3") (pinfunction "GND_3") (pintype "power_in"))
      (node (ref "IC2_ESP32S2WROOMM22S2") (pin "1") (pinfunction "GND_1_1") (pintype "bidirectional"))
      (node (ref "IC2_ESP32S2WROOMM22S2") (pin "26") (pinfunction "GND_2_26") (pintype "bidirectional"))
      (node (ref "IC2_ESP32S2WROOMM22S2") (pin "42") (pinfunction "GND_3_42") (pintype "bidirectional"))
      (node (ref "IC2_ESP32S2WROOMM22S2") (pin "43") (pinfunction "GND_4_43") (pintype "bidirectional"))
      (node (ref "IC2_ESP32S2WROOMM22S2") (pin "44") (pinfunction "GND_5_44") (pintype "bidirectional"))
      (node (ref "IC2_ESP32S2WROOMM22S2") (pin "45") (pinfunction "GND_6_45") (pintype "bidirectional"))
      (node (ref "IC2_ESP32S2WROOMM22S2") (pin "46") (pinfunction "GND_7_46") (pintype "bidirectional"))
      (node (ref "IC2_ESP32S2WROOMM22S2") (pin "47") (pinfunction "GND_8_47") (pintype "bidirectional"))
      (node (ref "IC2_ESP32S2WROOMM22S2") (pin "48") (pinfunction "GND_9_48") (pintype "bidirectional"))
      (node (ref "IC2_ESP32S2WROOMM22S2") (pin "49") (pinfunction "GND_10_49") (pintype "bidirectional"))
      (node (ref "IC2_ESP32S2WROOMM22S2") (pin "50") (pinfunction "GND_11_50") (pintype "bidirectional"))
      (node (ref "IC2_ESP32S2WROOMM22S2") (pin "51") (pinfunction "GND_12_51") (pintype "bidirectional"))
      (node (ref "IC4") (pin "10") (pinfunction "EP_2_10") (pintype "bidirectional"))
      (node (ref "IC4") (pin "11") (pinfunction "EP_3_11") (pintype "bidirectional"))
      (node (ref "IC4") (pin "12") (pinfunction "EP_4_12") (pintype "bidirectional"))
      (node (ref "IC4") (pin "13") (pinfunction "EP_5_13") (pintype "bidirectional"))
      (node (ref "IC4") (pin "7") (pinfunction "GND_7") (pintype "bidirectional"))
      (node (ref "IC4") (pin "9") (pinfunction "EP_1_9") (pintype "bidirectional"))
      (node (ref "J2") (pin "5") (pinfunction "5_5") (pintype "bidirectional"))
      (node (ref "J2") (pin "6") (pinfunction "6_6") (pintype "bidirectional"))
      (node (ref "J4_USB") (pin "MH1") (pinfunction "MH1_MH1") (pintype "bidirectional"))
      (node (ref "J4_USB") (pin "MH2") (pinfunction "MH2_MH2") (pintype "bidirectional"))
      (node (ref "J4_USB") (pin "MH3") (pinfunction "MH3_MH3") (pintype "bidirectional"))
      (node (ref "J4_USB") (pin "MH4") (pinfunction "MH4_MH4") (pintype "bidirectional"))
      (node (ref "J5_AUDIO") (pin "3") (pinfunction "RING_3") (pintype "bidirectional"))
      (node (ref "J6_OAT") (pin "1-S") (pinfunction "1_1-S") (pintype "bidirectional"))
      (node (ref "J7") (pin "2") (pinfunction "2_2") (pintype "bidirectional"))
      (node (ref "PS1") (pin "1") (pinfunction "GND_1") (pintype "power_in"))
      (node (ref "R11") (pin "1") (pinfunction "1_1") (pintype "passive"))
      (node (ref "R13") (pin "1") (pinfunction "1_1") (pintype "passive"))
      (node (ref "R28") (pin "2") (pinfunction "2_2") (pintype "passive"))
      (node (ref "R30") (pin "1") (pinfunction "1_1") (pintype "passive"))
      (node (ref "R33") (pin "1") (pinfunction "1_1") (pintype "passive"))
      (node (ref "SPI") (pin "1") (pinfunction "1_1") (pintype "passive"))
      (node (ref "U$1") (pin "1-GND") (pinfunction "GND_1-GND") (pintype "bidirectional"))
      (node (ref "U$4") (pin "1-GND") (pinfunction "1-GND_1-GND") (pintype "power_in"))
      (node (ref "U1") (pin "3") (pinfunction "RES_3") (pintype "power_in"))
      (node (ref "U1") (pin "8") (pinfunction "GND_8") (pintype "power_in"))
      (node (ref "U1") (pin "9") (pinfunction "GND_9") (pintype "power_in"))
      (node (ref "U10-MAG_SENSOR") (pin "11") (pinfunction "GND_11") (pintype "power_in"))
      (node (ref "U10-MAG_SENSOR") (pin "9") (pinfunction "GND_9") (pintype "power_in"))
      (node (ref "U11") (pin "1") (pinfunction "GND_1") (pintype "power_in"))
      (node (ref "U11") (pin "7") (pinfunction "GND_7") (pintype "power_in"))
      (node (ref "U12") (pin "2") (pinfunction "GND_2") (pintype "power_in"))
      (node (ref "U13-I2C") (pin "3") (pinfunction "GND_3") (pintype "power_in"))
      (node (ref "U13-I2C") (pin "7") (pinfunction "AD1_7") (pintype "input"))
      (node (ref "U13-I2C") (pin "8") (pinfunction "AD0_8") (pintype "input"))
      (node (ref "U2") (pin "3") (pinfunction "RES_3") (pintype "power_in"))
      (node (ref "U2") (pin "5") (pinfunction "SDO/SA0_5") (pintype "bidirectional"))
      (node (ref "U2") (pin "8") (pinfunction "GND_8") (pintype "power_in"))
      (node (ref "U2") (pin "9") (pinfunction "GND_9") (pintype "power_in"))
      (node (ref "U3-IMU") (pin "1") (pinfunction "SDO/SA0_1") (pintype "bidirectional"))
      (node (ref "U3-IMU") (pin "6") (pinfunction "GND_6") (pintype "power_in"))
      (node (ref "U3-IMU") (pin "7") (pinfunction "GND_7") (pintype "power_in"))
      (node (ref "U4") (pin "2") (pinfunction "GND_2") (pintype "power_in"))
      (node (ref "U5") (pin "2") (pinfunction "GND_2") (pintype "power_in"))
      (node (ref "U6") (pin "2") (pinfunction "GND_2") (pintype "power_in"))
      (node (ref "U7") (pin "2") (pinfunction "GND_2") (pintype "power_in"))
      (node (ref "UART0") (pin "3") (pinfunction "3_3") (pintype "passive"))
      (node (ref "UART1") (pin "3") (pinfunction "3_3") (pintype "passive"))
    )
    (net (code "22") (name "/GPIO0") (class "Default")
      (node (ref "C79") (pin "2") (pinfunction "2_2") (pintype "passive"))
      (node (ref "IC2_ESP32S2WROOMM22S2") (pin "3") (pinfunction "IO0_3") (pintype "bidirectional"))
      (node (ref "UART0") (pin "5") (pinfunction "5_5") (pintype "passive"))
    )
    (net (code "23") (name "/IO") (class "Default")
      (node (ref "C46") (pin "1") (pinfunction "1_1") (pintype "passive"))
      (node (ref "C64") (pin "1") (pinfunction "1_1") (pintype "passive"))
      (node (ref "J6_OAT") (pin "3-R") (pinfunction "3_3-R") (pintype "bidirectional"))
      (node (ref "U13-I2C") (pin "2") (pinfunction "IO_2") (pintype "bidirectional"))
    )
    (net (code "24") (name "/MISO") (class "Default")
      (node (ref "J7") (pin "7") (pinfunction "7_7") (pintype "bidirectional"))
    )
    (net (code "25") (name "/MOSI") (class "Default")
      (node (ref "J7") (pin "8") (pinfunction "8_8") (pintype "bidirectional"))
    )
    (net (code "26") (name "/SCL0") (class "Default")
      (node (ref "C55") (pin "2") (pinfunction "2_2") (pintype "passive"))
      (node (ref "DLHR-L30G-E1BD-C-NAV8") (pin "4-SCL") (pinfunction "4-SCL_4-SCL") (pintype "bidirectional"))
      (node (ref "IC2_ESP32S2WROOMM22S2") (pin "17") (pinfunction "IO14_17") (pintype "bidirectional"))
      (node (ref "J2") (pin "4") (pinfunction "4_4") (pintype "bidirectional"))
      (node (ref "R2") (pin "2") (pinfunction "2_2") (pintype "passive"))
      (node (ref "SJ2-I2C") (pin "1") (pinfunction "1_1") (pintype "passive"))
      (node (ref "U$1") (pin "4-SCL") (pinfunction "SCL_4-SCL") (pintype "bidirectional"))
      (node (ref "U$4") (pin "4-SCL") (pinfunction "4-SCL_4-SCL") (pintype "bidirectional"))
      (node (ref "U1") (pin "2") (pinfunction "SCL/SPC_2") (pintype "input"))
      (node (ref "U10-MAG_SENSOR") (pin "1") (pinfunction "SCL/SCLK_1") (pintype "bidirectional"))
      (node (ref "U13-I2C") (pin "4") (pinfunction "SCL_4") (pintype "input"))
      (node (ref "U2") (pin "2") (pinfunction "SCL/SPC_2") (pintype "input"))
      (node (ref "U3-IMU") (pin "13") (pinfunction "SCL/SPC_13") (pintype "input"))
    )
    (net (code "27") (name "/SCL1") (class "Default")
      (node (ref "C50") (pin "2") (pinfunction "2_2") (pintype "passive"))
      (node (ref "C59") (pin "2") (pinfunction "2_2") (pintype "passive"))
      (node (ref "IC2_ESP32S2WROOMM22S2") (pin "19") (pinfunction "IO16_19") (pintype "bidirectional"))
      (node (ref "J7") (pin "5") (pinfunction "5_5") (pintype "bidirectional"))
      (node (ref "R24") (pin "2") (pinfunction "2_2") (pintype "passive"))
      (node (ref "SJ2-I2C") (pin "2") (pinfunction "2_2") (pintype "passive"))
    )
    (net (code "28") (name "/SDA0") (class "Default")
      (node (ref "C43") (pin "2") (pinfunction "2_2") (pintype "passive"))
      (node (ref "DLHR-L30G-E1BD-C-NAV8") (pin "3-SDA") (pinfunction "3-SDA_3-SDA") (pintype "bidirectional"))
      (node (ref "I2C_LINK") (pin "1") (pinfunction "1_1") (pintype "passive"))
      (node (ref "IC2_ESP32S2WROOMM22S2") (pin "16") (pinfunction "IO13_16") (pintype "bidirectional"))
      (node (ref "J2") (pin "3") (pinfunction "3_3") (pintype "bidirectional"))
      (node (ref "R1") (pin "2") (pinfunction "2_2") (pintype "passive"))
      (node (ref "U$1") (pin "3-SDA") (pinfunction "SDA_3-SDA") (pintype "bidirectional"))
      (node (ref "U$4") (pin "3-SDA") (pinfunction "3-SDA_3-SDA") (pintype "bidirectional"))
      (node (ref "U1") (pin "4") (pinfunction "SDA/SDI/SDO_4") (pintype "bidirectional"))
      (node (ref "U10-MAG_SENSOR") (pin "16") (pinfunction "SDA/SDI_16") (pintype "bidirectional"))
      (node (ref "U13-I2C") (pin "5") (pinfunction "SDA_5") (pintype "bidirectional"))
      (node (ref "U2") (pin "4") (pinfunction "SDA/SDI/SDO_4") (pintype "bidirectional"))
      (node (ref "U3-IMU") (pin "14") (pinfunction "SDA/SDI/SDO_14") (pintype "bidirectional"))
    )
    (net (code "29") (name "/SDA1") (class "Default")
      (node (ref "C53") (pin "2") (pinfunction "2_2") (pintype "passive"))
      (node (ref "C60") (pin "2") (pinfunction "2_2") (pintype "passive"))
      (node (ref "I2C_LINK") (pin "2") (pinfunction "2_2") (pintype "passive"))
      (node (ref "IC2_ESP32S2WROOMM22S2") (pin "18") (pinfunction "IO15_18") (pintype "bidirectional"))
      (node (ref "J7") (pin "6") (pinfunction "6_6") (pintype "bidirectional"))
      (node (ref "R23") (pin "2") (pinfunction "2_2") (pintype "passive"))
    )
    (net (code "30") (name "/U0RXD") (class "Default")
      (node (ref "C77") (pin "2") (pinfunction "2_2") (pintype "passive"))
      (node (ref "IC2_ESP32S2WROOMM22S2") (pin "38") (pinfunction "RXD0_38") (pintype "bidirectional"))
      (node (ref "UART0") (pin "2") (pinfunction "2_2") (pintype "passive"))
    )
    (net (code "31") (name "/U0TXD") (class "Default")
      (node (ref "C76") (pin "2") (pinfunction "2_2") (pintype "passive"))
      (node (ref "IC2_ESP32S2WROOMM22S2") (pin "37") (pinfunction "TXD0_37") (pintype "bidirectional"))
      (node (ref "UART0") (pin "1") (pinfunction "1_1") (pintype "passive"))
    )
    (net (code "32") (name "/U1RXD") (class "Default")
      (node (ref "C74") (pin "1") (pinfunction "1_1") (pintype "passive"))
      (node (ref "IC2_ESP32S2WROOMM22S2") (pin "21") (pinfunction "IO18_21") (pintype "bidirectional"))
      (node (ref "UART1") (pin "2") (pinfunction "2_2") (pintype "passive"))
    )
    (net (code "33") (name "/U1TXD") (class "Default")
      (node (ref "C75") (pin "1") (pinfunction "1_1") (pintype "passive"))
      (node (ref "IC2_ESP32S2WROOMM22S2") (pin "20") (pinfunction "IO17_20") (pintype "bidirectional"))
      (node (ref "UART1") (pin "1") (pinfunction "1_1") (pintype "passive"))
    )
    (net (code "34") (name "/USB_D+") (class "Default")
      (node (ref "IC2_ESP32S2WROOMM22S2") (pin "23") (pinfunction "IO20_23") (pintype "bidirectional"))
      (node (ref "R16") (pin "2") (pinfunction "2_2") (pintype "passive"))
    )
    (net (code "35") (name "/USB_D-") (class "Default")
      (node (ref "IC2_ESP32S2WROOMM22S2") (pin "22") (pinfunction "IO19_22") (pintype "bidirectional"))
      (node (ref "R17") (pin "2") (pinfunction "2_2") (pintype "passive"))
    )
    (net (code "36") (name "/VDD1") (class "Default")
      (node (ref "C72") (pin "1") (pinfunction "1_1") (pintype "passive"))
      (node (ref "R20") (pin "1") (pinfunction "1_1") (pintype "passive"))
      (node (ref "U7") (pin "5") (pinfunction "OUT_5") (pintype "output"))
    )
    (net (code "37") (name "/VDD1F") (class "Default")
      (node (ref "C1") (pin "1") (pinfunction "1_1") (pintype "passive"))
      (node (ref "R41") (pin "2") (pinfunction "2_2") (pintype "passive"))
      (node (ref "U1") (pin "10") (pinfunction "VDD_10") (pintype "power_in"))
    )
    (net (code "38") (name "/VDD1FIO") (class "Default")
      (node (ref "C38") (pin "1") (pinfunction "1_1") (pintype "passive"))
      (node (ref "R40") (pin "2") (pinfunction "2_2") (pintype "passive"))
      (node (ref "U1") (pin "1") (pinfunction "VDD_IO_1") (pintype "power_in"))
      (node (ref "U1") (pin "5") (pinfunction "SDO/SA0_5") (pintype "bidirectional"))
      (node (ref "U1") (pin "6") (pinfunction "CS_6") (pintype "input"))
    )
    (net (code "39") (name "/VDD2") (class "Default")
      (node (ref "C62") (pin "1") (pinfunction "1_1") (pintype "passive"))
      (node (ref "R19") (pin "1") (pinfunction "1_1") (pintype "passive"))
      (node (ref "U6") (pin "5") (pinfunction "OUT_5") (pintype "output"))
    )
    (net (code "40") (name "/VDD2F") (class "Default")
      (node (ref "C2") (pin "1") (pinfunction "1_1") (pintype "passive"))
      (node (ref "R38") (pin "2") (pinfunction "2_2") (pintype "passive"))
      (node (ref "U2") (pin "10") (pinfunction "VDD_10") (pintype "power_in"))
    )
    (net (code "41") (name "/VDD2FIO") (class "Default")
      (node (ref "C36") (pin "1") (pinfunction "1_1") (pintype "passive"))
      (node (ref "R39") (pin "2") (pinfunction "2_2") (pintype "passive"))
      (node (ref "U2") (pin "1") (pinfunction "VDD_IO_1") (pintype "power_in"))
      (node (ref "U2") (pin "6") (pinfunction "CS_6") (pintype "input"))
    )
    (net (code "42") (name "/VDD3") (class "Default")
      (node (ref "C52") (pin "1") (pinfunction "1_1") (pintype "passive"))
      (node (ref "R18") (pin "1") (pinfunction "1_1") (pintype "passive"))
      (node (ref "U5") (pin "5") (pinfunction "OUT_5") (pintype "output"))
    )
    (net (code "43") (name "/VDD3F") (class "Default")
      (node (ref "C11") (pin "1") (pinfunction "1_1") (pintype "passive"))
      (node (ref "R36") (pin "2") (pinfunction "2_2") (pintype "passive"))
      (node (ref "U3-IMU") (pin "8") (pinfunction "VDD_8") (pintype "power_in"))
    )
    (net (code "44") (name "/VDD3FIO") (class "Default")
      (node (ref "C39") (pin "1") (pinfunction "1_1") (pintype "passive"))
      (node (ref "R37") (pin "2") (pinfunction "2_2") (pintype "passive"))
      (node (ref "U3-IMU") (pin "12") (pinfunction "CS_12") (pintype "input"))
      (node (ref "U3-IMU") (pin "5") (pinfunction "VDDIO_5") (pintype "power_in"))
    )
    (net (code "45") (name "/VDD4") (class "Default")
      (node (ref "C42") (pin "1") (pinfunction "1_1") (pintype "passive"))
      (node (ref "R13") (pin "2") (pinfunction "2_2") (pintype "passive"))
      (node (ref "R21") (pin "1") (pinfunction "1_1") (pintype "passive"))
      (node (ref "U4") (pin "5") (pinfunction "OUT_5") (pintype "output"))
    )
    (net (code "46") (name "/VDD4F") (class "Default")
      (node (ref "C16") (pin "1") (pinfunction "1_1") (pintype "passive"))
      (node (ref "C3") (pin "1") (pinfunction "1_1") (pintype "passive"))
      (node (ref "C35") (pin "1") (pinfunction "1_1") (pintype "passive"))
      (node (ref "DLHR-L30G-E1BD-C-NAV8") (pin "2-VS") (pinfunction "2-VS_2-VS") (pintype "power_in"))
      (node (ref "R21") (pin "2") (pinfunction "2_2") (pintype "passive"))
      (node (ref "U$1") (pin "2-VCC") (pinfunction "VCC_2-VCC") (pintype "bidirectional"))
      (node (ref "U$4") (pin "2-VS") (pinfunction "2-VS_2-VS") (pintype "power_in"))
    )
    (net (code "47") (name "/VDD5") (class "Default")
      (node (ref "C10") (pin "1") (pinfunction "1_1") (pintype "passive"))
      (node (ref "R22") (pin "1") (pinfunction "1_1") (pintype "passive"))
      (node (ref "U12") (pin "5") (pinfunction "OUT_5") (pintype "output"))
    )
    (net (code "48") (name "/VDD5F") (class "Default")
      (node (ref "C9") (pin "1") (pinfunction "1_1") (pintype "passive"))
      (node (ref "R12") (pin "2") (pinfunction "2_2") (pintype "passive"))
      (node (ref "U10-MAG_SENSOR") (pin "2") (pinfunction "VDD_2") (pintype "power_in"))
    )
    (net (code "49") (name "/VDD5FIO") (class "Default")
      (node (ref "C7") (pin "1") (pinfunction "1_1") (pintype "passive"))
      (node (ref "R34") (pin "2") (pinfunction "2_2") (pintype "passive"))
      (node (ref "U10-MAG_SENSOR") (pin "13") (pinfunction "VDDIO_13") (pintype "power_in"))
      (node (ref "U10-MAG_SENSOR") (pin "4") (pinfunction "CS_4") (pintype "input"))
    )
    (net (code "50") (name "/V_SNS") (class "Default")
      (node (ref "C34") (pin "1") (pinfunction "1_1") (pintype "passive"))
      (node (ref "IC2_ESP32S2WROOMM22S2") (pin "11") (pinfunction "IO8_11") (pintype "bidirectional"))
      (node (ref "R28") (pin "1") (pinfunction "1_1") (pintype "passive"))
      (node (ref "R31") (pin "2") (pinfunction "2_2") (pintype "passive"))
    )
    (net (code "51") (name "Net-(12V_INA-S)") (class "Default")
      (node (ref "12V_IN") (pin "1") (pinfunction "S_1") (pintype "passive"))
      (node (ref "F1") (pin "1") (pinfunction "1_1") (pintype "bidirectional"))
    )
    (net (code "52") (name "Net-(C14-Pad1)") (class "Default")
      (node (ref "C14") (pin "1") (pinfunction "1_1") (pintype "passive"))
      (node (ref "R20") (pin "2") (pinfunction "2_2") (pintype "passive"))
      (node (ref "R40") (pin "1") (pinfunction "1_1") (pintype "passive"))
      (node (ref "R41") (pin "1") (pinfunction "1_1") (pintype "passive"))
    )
    (net (code "53") (name "Net-(C15-Pad1)") (class "Default")
      (node (ref "C15") (pin "1") (pinfunction "1_1") (pintype "passive"))
      (node (ref "R19") (pin "2") (pinfunction "2_2") (pintype "passive"))
      (node (ref "R38") (pin "1") (pinfunction "1_1") (pintype "passive"))
      (node (ref "R39") (pin "1") (pinfunction "1_1") (pintype "passive"))
    )
    (net (code "54") (name "Net-(C25-Pad1)") (class "Default")
      (node (ref "C25") (pin "1") (pinfunction "1_1") (pintype "passive"))
      (node (ref "R27") (pin "2") (pinfunction "2_2") (pintype "passive"))
    )
    (net (code "55") (name "Net-(C25-Pad2)") (class "Default")
      (node (ref "C25") (pin "2") (pinfunction "2_2") (pintype "passive"))
      (node (ref "C33") (pin "2") (pinfunction "2_2") (pintype "passive"))
      (node (ref "R15") (pin "1") (pinfunction "1_1") (pintype "passive"))
    )
    (net (code "56") (name "Net-(C26-Pad2)") (class "Default")
      (node (ref "C26") (pin "2") (pinfunction "2_2") (pintype "passive"))
      (node (ref "R14") (pin "1") (pinfunction "1_1") (pintype "passive"))
    )
    (net (code "57") (name "Net-(C33-Pad1)") (class "Default")
      (node (ref "C33") (pin "1") (pinfunction "1_1") (pintype "passive"))
      (node (ref "R26") (pin "2") (pinfunction "2_2") (pintype "passive"))
    )
    (net (code "58") (name "Net-(C37-Pad1)") (class "Default")
      (node (ref "C37") (pin "1") (pinfunction "1_1") (pintype "passive"))
      (node (ref "R18") (pin "2") (pinfunction "2_2") (pintype "passive"))
      (node (ref "R36") (pin "1") (pinfunction "1_1") (pintype "passive"))
      (node (ref "R37") (pin "1") (pinfunction "1_1") (pintype "passive"))
    )
    (net (code "59") (name "Net-(C40-Pad1)") (class "Default")
      (node (ref "C40") (pin "1") (pinfunction "1_1") (pintype "passive"))
      (node (ref "R12") (pin "1") (pinfunction "1_1") (pintype "passive"))
      (node (ref "R22") (pin "2") (pinfunction "2_2") (pintype "passive"))
      (node (ref "R34") (pin "1") (pinfunction "1_1") (pintype "passive"))
    )
    (net (code "60") (name "Net-(D1-A)") (class "Default")
      (node (ref "C48") (pin "2") (pinfunction "2_2") (pintype "passive"))
      (node (ref "D1") (pin "2") (pinfunction "A_2") (pintype "bidirectional"))
      (node (ref "F1") (pin "2") (pinfunction "2_2") (pintype "bidirectional"))
      (node (ref "R31") (pin "1") (pinfunction "1_1") (pintype "passive"))
    )
    (net (code "61") (name "Net-(D1-K)") (class "Default")
      (node (ref "C17") (pin "2") (pinfunction "2_2") (pintype "bidirectional"))
      (node (ref "D1") (pin "1") (pinfunction "K_1") (pintype "bidirectional"))
      (node (ref "L1") (pin "1") (pinfunction "1_1") (pintype "bidirectional"))
    )
    (net (code "62") (name "Net-(D2-A)") (class "Default")
      (node (ref "C20") (pin "1") (pinfunction "1_1") (pintype "passive"))
      (node (ref "C21") (pin "2") (pinfunction "2_2") (pintype "bidirectional"))
      (node (ref "D2") (pin "2") (pinfunction "A_2") (pintype "bidirectional"))
      (node (ref "L2") (pin "2") (pinfunction "2_2") (pintype "bidirectional"))
      (node (ref "R9") (pin "2") (pinfunction "2_2") (pintype "passive"))
    )
    (net (code "63") (name "Net-(D4-CATHODE)") (class "Default")
      (node (ref "C30") (pin "1") (pinfunction "1_1") (pintype "passive"))
      (node (ref "D4") (pin "1") (pinfunction "CATHODE_1") (pintype "bidirectional"))
      (node (ref "J4_USB") (pin "1") (pinfunction "1_1") (pintype "bidirectional"))
      (node (ref "R29") (pin "2") (pinfunction "2_2") (pintype "passive"))
    )
    (net (code "64") (name "Net-(IC1-D_1)") (class "Default")
      (node (ref "IC1") (pin "1") (pinfunction "D_1_1") (pintype "bidirectional"))
      (node (ref "R17") (pin "1") (pinfunction "1_1") (pintype "passive"))
    )
    (net (code "65") (name "Net-(IC1-D_2)") (class "Default")
      (node (ref "IC1") (pin "2") (pinfunction "D_2_2") (pintype "bidirectional"))
      (node (ref "R16") (pin "1") (pinfunction "1_1") (pintype "passive"))
    )
    (net (code "66") (name "Net-(IC2_ESP32S2WROOMM22S2-IO42)") (class "Default")
      (node (ref "IC2_ESP32S2WROOMM22S2") (pin "36") (pinfunction "IO42_36") (pintype "bidirectional"))
      (node (ref "WIFI_EN") (pin "1") (pinfunction "1_1") (pintype "passive"))
    )
    (net (code "67") (name "Net-(IC4-BYPASS)") (class "Default")
      (node (ref "C27") (pin "1") (pinfunction "1_1") (pintype "passive"))
      (node (ref "IC4") (pin "2") (pinfunction "BYPASS_2") (pintype "bidirectional"))
    )
    (net (code "68") (name "Net-(IC4-IN+)") (class "Default")
      (node (ref "C24") (pin "1") (pinfunction "1_1") (pintype "passive"))
      (node (ref "IC4") (pin "3") (pinfunction "IN+_3") (pintype "bidirectional"))
      (node (ref "R14") (pin "2") (pinfunction "2_2") (pintype "passive"))
    )
    (net (code "69") (name "Net-(IC4-IN-)") (class "Default")
      (node (ref "C23") (pin "1") (pinfunction "1_1") (pintype "passive"))
      (node (ref "IC4") (pin "4") (pinfunction "IN-_4") (pintype "bidirectional"))
      (node (ref "R15") (pin "2") (pinfunction "2_2") (pintype "passive"))
    )
    (net (code "70") (name "Net-(J4_USB-Pad4)") (class "Default")
      (node (ref "J4_USB") (pin "4") (pinfunction "4_4") (pintype "bidirectional"))
      (node (ref "R30") (pin "2") (pinfunction "2_2") (pintype "passive"))
    )
    (net (code "71") (name "Net-(PS1-BST)") (class "Default")
      (node (ref "C19") (pin "2") (pinfunction "2_2") (pintype "passive"))
      (node (ref "PS1") (pin "6") (pinfunction "BST_6") (pintype "input"))
    )
    (net (code "72") (name "Net-(PS1-EN)") (class "Default")
      (node (ref "C18") (pin "2") (pinfunction "2_2") (pintype "bidirectional"))
      (node (ref "L1") (pin "2") (pinfunction "2_2") (pintype "bidirectional"))
      (node (ref "PS1") (pin "3") (pinfunction "IN_3") (pintype "input"))
      (node (ref "PS1") (pin "5") (pinfunction "EN_5") (pintype "input"))
    )
    (net (code "73") (name "Net-(PS1-FB)") (class "Default")
      (node (ref "C20") (pin "2") (pinfunction "2_2") (pintype "passive"))
      (node (ref "PS1") (pin "4") (pinfunction "FB_4") (pintype "input"))
      (node (ref "R11") (pin "2") (pinfunction "2_2") (pintype "passive"))
      (node (ref "R9") (pin "1") (pinfunction "1_1") (pintype "passive"))
    )
    (net (code "74") (name "Net-(PS1-SW)") (class "Default")
      (node (ref "C19") (pin "1") (pinfunction "1_1") (pintype "passive"))
      (node (ref "L2") (pin "1") (pinfunction "1_1") (pintype "bidirectional"))
      (node (ref "PS1") (pin "2") (pinfunction "SW_2") (pintype "output"))
    )
    (net (code "75") (name "Net-(U4-EN)") (class "Default")
      (node (ref "C41") (pin "1") (pinfunction "1_1") (pintype "passive"))
      (node (ref "R6") (pin "2") (pinfunction "2_2") (pintype "passive"))
      (node (ref "U4") (pin "1") (pinfunction "IN_1") (pintype "input"))
      (node (ref "U4") (pin "3") (pinfunction "EN_3") (pintype "input"))
    )
    (net (code "76") (name "Net-(U5-EN)") (class "Default")
      (node (ref "C51") (pin "1") (pinfunction "1_1") (pintype "passive"))
      (node (ref "R5") (pin "2") (pinfunction "2_2") (pintype "passive"))
      (node (ref "U5") (pin "1") (pinfunction "IN_1") (pintype "input"))
      (node (ref "U5") (pin "3") (pinfunction "EN_3") (pintype "input"))
    )
    (net (code "77") (name "Net-(U6-EN)") (class "Default")
      (node (ref "C61") (pin "1") (pinfunction "1_1") (pintype "passive"))
      (node (ref "R4") (pin "2") (pinfunction "2_2") (pintype "passive"))
      (node (ref "U6") (pin "1") (pinfunction "IN_1") (pintype "input"))
      (node (ref "U6") (pin "3") (pinfunction "EN_3") (pintype "input"))
    )
    (net (code "78") (name "Net-(U7-EN)") (class "Default")
      (node (ref "C71") (pin "1") (pinfunction "1_1") (pintype "passive"))
      (node (ref "R3") (pin "2") (pinfunction "2_2") (pintype "passive"))
      (node (ref "U7") (pin "1") (pinfunction "IN_1") (pintype "input"))
      (node (ref "U7") (pin "3") (pinfunction "EN_3") (pintype "input"))
    )
    (net (code "79") (name "Net-(U10-MAG_SENSOR-CAP)") (class "Default")
      (node (ref "C8") (pin "1") (pinfunction "1_1") (pintype "passive"))
      (node (ref "U10-MAG_SENSOR") (pin "10") (pinfunction "CAP_10") (pintype "power_in"))
    )
    (net (code "80") (name "Net-(U11-EN)") (class "Default")
      (node (ref "C5") (pin "1") (pinfunction "1_1") (pintype "passive"))
      (node (ref "R8") (pin "2") (pinfunction "2_2") (pintype "passive"))
      (node (ref "U11") (pin "4") (pinfunction "VIN_4") (pintype "input"))
      (node (ref "U11") (pin "6") (pinfunction "EN_6") (pintype "input"))
    )
    (net (code "81") (name "Net-(U11-SENSE)") (class "Default")
      (node (ref "R32") (pin "1") (pinfunction "1_1") (pintype "passive"))
      (node (ref "R33") (pin "2") (pinfunction "2_2") (pintype "passive"))
      (node (ref "U11") (pin "2") (pinfunction "SENSE_2") (pintype "input"))
    )
    (net (code "82") (name "Net-(U12-EN)") (class "Default")
      (node (ref "C12") (pin "1") (pinfunction "1_1") (pintype "passive"))
      (node (ref "R7") (pin "2") (pinfunction "2_2") (pintype "passive"))
      (node (ref "U12") (pin "1") (pinfunction "IN_1") (pintype "input"))
      (node (ref "U12") (pin "3") (pinfunction "EN_3") (pintype "input"))
    )
    (net (code "83") (name "unconnected-(DLHR-L30G-E1BD-C-NAV8-8-{slash}SS-Pad8-SS)") (class "Default")
      (node (ref "DLHR-L30G-E1BD-C-NAV8") (pin "8-SS") (pinfunction "8-/SS_8-SS") (pintype "bidirectional"))
    )
    (net (code "84") (name "unconnected-(DLHR-L30G-E1BD-C-NAV8-Pad5-EOC)") (class "Default")
      (node (ref "DLHR-L30G-E1BD-C-NAV8") (pin "5-EOC") (pinfunction "5-EOC_5-EOC") (pintype "bidirectional"))
    )
    (net (code "85") (name "unconnected-(DLHR-L30G-E1BD-C-NAV8-Pad6-MISO)") (class "Default")
      (node (ref "DLHR-L30G-E1BD-C-NAV8") (pin "6-MISO") (pinfunction "6-MISO_6-MISO") (pintype "bidirectional"))
    )
    (net (code "86") (name "unconnected-(DLHR-L30G-E1BD-C-NAV8-Pad7-NC)") (class "Default")
      (node (ref "DLHR-L30G-E1BD-C-NAV8") (pin "7-NC") (pinfunction "7-NC_7-NC") (pintype "bidirectional"))
    )
    (net (code "87") (name "unconnected-(IC1-NC-Pad4)") (class "Default")
      (node (ref "IC1") (pin "4") (pinfunction "NC_4") (pintype "no_connect"))
    )
    (net (code "88") (name "unconnected-(IC2_ESP32S2WROOMM22S2-IO1-Pad4)") (class "Default")
      (node (ref "IC2_ESP32S2WROOMM22S2") (pin "4") (pinfunction "IO1_4") (pintype "bidirectional"))
    )
    (net (code "89") (name "unconnected-(IC2_ESP32S2WROOMM22S2-IO2-Pad5)") (class "Default")
      (node (ref "IC2_ESP32S2WROOMM22S2") (pin "5") (pinfunction "IO2_5") (pintype "bidirectional"))
    )
    (net (code "90") (name "unconnected-(IC2_ESP32S2WROOMM22S2-IO3-Pad6)") (class "Default")
      (node (ref "IC2_ESP32S2WROOMM22S2") (pin "6") (pinfunction "IO3_6") (pintype "bidirectional"))
    )
    (net (code "91") (name "unconnected-(IC2_ESP32S2WROOMM22S2-IO4-Pad7)") (class "Default")
      (node (ref "IC2_ESP32S2WROOMM22S2") (pin "7") (pinfunction "IO4_7") (pintype "bidirectional"))
    )
    (net (code "92") (name "unconnected-(IC2_ESP32S2WROOMM22S2-IO5-Pad8)") (class "Default")
      (node (ref "IC2_ESP32S2WROOMM22S2") (pin "8") (pinfunction "IO5_8") (pintype "bidirectional"))
    )
    (net (code "93") (name "unconnected-(IC2_ESP32S2WROOMM22S2-IO6-Pad9)") (class "Default")
      (node (ref "IC2_ESP32S2WROOMM22S2") (pin "9") (pinfunction "IO6_9") (pintype "bidirectional"))
    )
    (net (code "94") (name "unconnected-(IC2_ESP32S2WROOMM22S2-IO7-Pad10)") (class "Default")
      (node (ref "IC2_ESP32S2WROOMM22S2") (pin "10") (pinfunction "IO7_10") (pintype "bidirectional"))
    )
    (net (code "95") (name "unconnected-(IC2_ESP32S2WROOMM22S2-IO9-Pad12)") (class "Default")
      (node (ref "IC2_ESP32S2WROOMM22S2") (pin "12") (pinfunction "IO9_12") (pintype "bidirectional"))
    )
    (net (code "96") (name "unconnected-(IC2_ESP32S2WROOMM22S2-IO10-Pad13)") (class "Default")
      (node (ref "IC2_ESP32S2WROOMM22S2") (pin "13") (pinfunction "IO10_13") (pintype "bidirectional"))
    )
    (net (code "97") (name "unconnected-(IC2_ESP32S2WROOMM22S2-IO11-Pad14)") (class "Default")
      (node (ref "IC2_ESP32S2WROOMM22S2") (pin "14") (pinfunction "IO11_14") (pintype "bidirectional"))
    )
    (net (code "98") (name "unconnected-(IC2_ESP32S2WROOMM22S2-IO12-Pad15)") (class "Default")
      (node (ref "IC2_ESP32S2WROOMM22S2") (pin "15") (pinfunction "IO12_15") (pintype "bidirectional"))
    )
    (net (code "99") (name "unconnected-(IC2_ESP32S2WROOMM22S2-IO21-Pad24)") (class "Default")
      (node (ref "IC2_ESP32S2WROOMM22S2") (pin "24") (pinfunction "IO21_24") (pintype "bidirectional"))
    )
    (net (code "100") (name "unconnected-(IC2_ESP32S2WROOMM22S2-IO26-Pad25)") (class "Default")
      (node (ref "IC2_ESP32S2WROOMM22S2") (pin "25") (pinfunction "IO26_25") (pintype "bidirectional"))
    )
    (net (code "101") (name "unconnected-(IC2_ESP32S2WROOMM22S2-IO33-Pad27)") (class "Default")
      (node (ref "IC2_ESP32S2WROOMM22S2") (pin "27") (pinfunction "IO33_27") (pintype "bidirectional"))
    )
    (net (code "102") (name "unconnected-(IC2_ESP32S2WROOMM22S2-IO38-Pad32)") (class "Default")
      (node (ref "IC2_ESP32S2WROOMM22S2") (pin "32") (pinfunction "IO38_32") (pintype "bidirectional"))
    )
    (net (code "103") (name "unconnected-(IC2_ESP32S2WROOMM22S2-IO39-Pad33)") (class "Default")
      (node (ref "IC2_ESP32S2WROOMM22S2") (pin "33") (pinfunction "IO39_33") (pintype "bidirectional"))
    )
    (net (code "104") (name "unconnected-(IC2_ESP32S2WROOMM22S2-IO40-Pad34)") (class "Default")
      (node (ref "IC2_ESP32S2WROOMM22S2") (pin "34") (pinfunction "IO40_34") (pintype "bidirectional"))
    )
    (net (code "105") (name "unconnected-(IC2_ESP32S2WROOMM22S2-IO45-Pad39)") (class "Default")
      (node (ref "IC2_ESP32S2WROOMM22S2") (pin "39") (pinfunction "IO45_39") (pintype "bidirectional"))
    )
    (net (code "106") (name "unconnected-(IC2_ESP32S2WROOMM22S2-IO46-Pad40)") (class "Default")
      (node (ref "IC2_ESP32S2WROOMM22S2") (pin "40") (pinfunction "IO46_40") (pintype "bidirectional"))
    )
    (net (code "107") (name "unconnected-(J6_OAT-Pad4)") (class "Default")
      (node (ref "J6_OAT") (pin "4") (pinfunction "4_4") (pintype "bidirectional"))
    )
    (net (code "108") (name "unconnected-(U$4-Pad5-INT{slash}SS)") (class "Default")
      (node (ref "U$4") (pin "5-INT/SS") (pinfunction "5-INT/SS_5-INT/SS") (pintype "bidirectional"))
    )
    (net (code "109") (name "unconnected-(U$4-Pad6-NC)") (class "Default")
      (node (ref "U$4") (pin "6-NC") (pinfunction "6-NC_6-NC") (pintype "bidirectional"))
    )
    (net (code "110") (name "unconnected-(U$4-Pad7-NC)") (class "Default")
      (node (ref "U$4") (pin "7-NC") (pinfunction "7-NC_7-NC") (pintype "bidirectional"))
    )
    (net (code "111") (name "unconnected-(U$4-Pad8-NC)") (class "Default")
      (node (ref "U$4") (pin "8-NC") (pinfunction "8-NC_8-NC") (pintype "bidirectional"))
    )
    (net (code "112") (name "unconnected-(U1-INT_DRDY-Pad7)") (class "Default")
      (node (ref "U1") (pin "7") (pinfunction "INT_DRDY_7") (pintype "output"))
    )
    (net (code "113") (name "unconnected-(U2-INT_DRDY-Pad7)") (class "Default")
      (node (ref "U2") (pin "7") (pinfunction "INT_DRDY_7") (pintype "output"))
    )
    (net (code "114") (name "unconnected-(U3-IMU-INT1-Pad4)") (class "Default")
      (node (ref "U3-IMU") (pin "4") (pinfunction "INT1_4") (pintype "input"))
    )
    (net (code "115") (name "unconnected-(U3-IMU-INT2{slash}DEN{slash}MDRDY-Pad9)") (class "Default")
      (node (ref "U3-IMU") (pin "9") (pinfunction "INT2/DEN/MDRDY_9") (pintype "input"))
    )
    (net (code "116") (name "unconnected-(U3-IMU-OCS_AUX-Pad10)") (class "Default")
      (node (ref "U3-IMU") (pin "10") (pinfunction "OCS_AUX_10") (pintype "input"))
    )
    (net (code "117") (name "unconnected-(U3-IMU-SCX-Pad3)") (class "Default")
      (node (ref "U3-IMU") (pin "3") (pinfunction "SCX_3") (pintype "bidirectional"))
    )
    (net (code "118") (name "unconnected-(U3-IMU-SDO_AUX-Pad11)") (class "Default")
      (node (ref "U3-IMU") (pin "11") (pinfunction "SDO_AUX_11") (pintype "bidirectional"))
    )
    (net (code "119") (name "unconnected-(U3-IMU-SDX-Pad2)") (class "Default")
      (node (ref "U3-IMU") (pin "2") (pinfunction "SDX_2") (pintype "bidirectional"))
    )
    (net (code "120") (name "unconnected-(U10-MAG_SENSOR-INT-Pad15)") (class "Default")
      (node (ref "U10-MAG_SENSOR") (pin "15") (pinfunction "INT_15") (pintype "output"))
    )
    (net (code "121") (name "unconnected-(U10-MAG_SENSOR-SDO-Pad5)") (class "Default")
      (node (ref "U10-MAG_SENSOR") (pin "5") (pinfunction "SDO_5") (pintype "bidirectional"))
    )
    (net (code "122") (name "unconnected-(U13-I2C-PCTLZ-Pad6)") (class "Default")
      (node (ref "U13-I2C") (pin "6") (pinfunction "PCTLZ_6") (pintype "output"))
    )
  )
)
